# 1400-1a.net
KiCad netlist of a schematic drawn in EAGLE
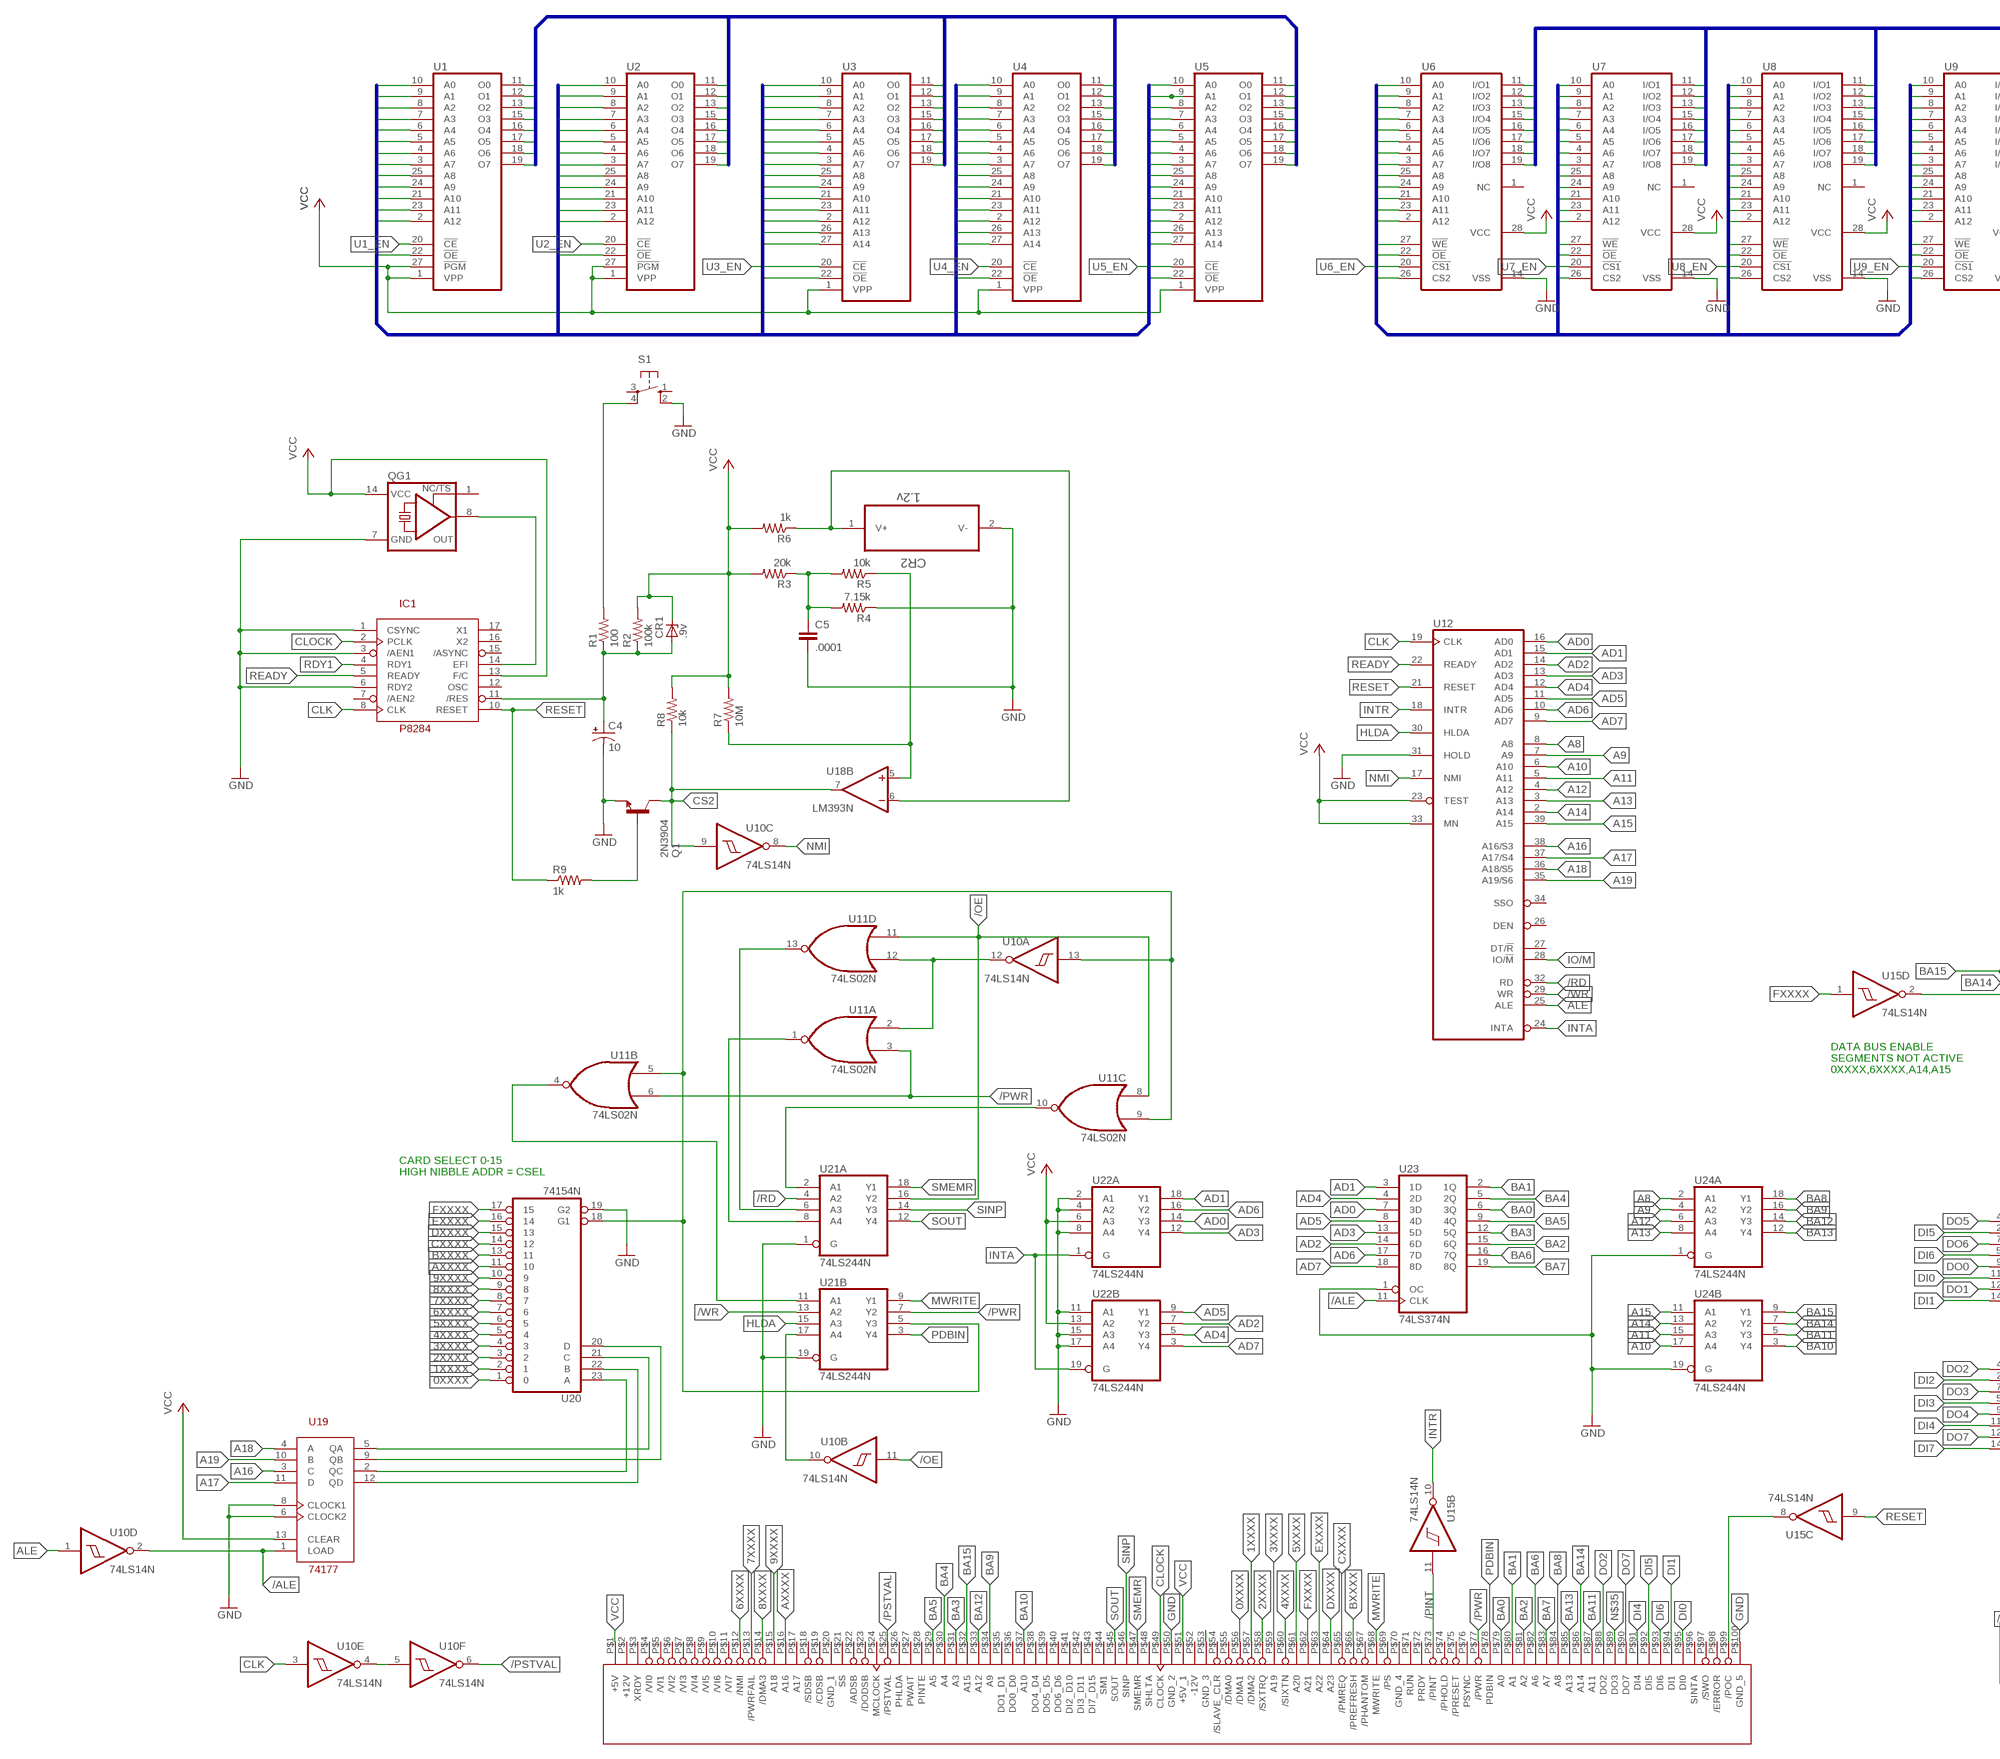
[diagram p0: schematic, sheet 1, part 1 of 2]
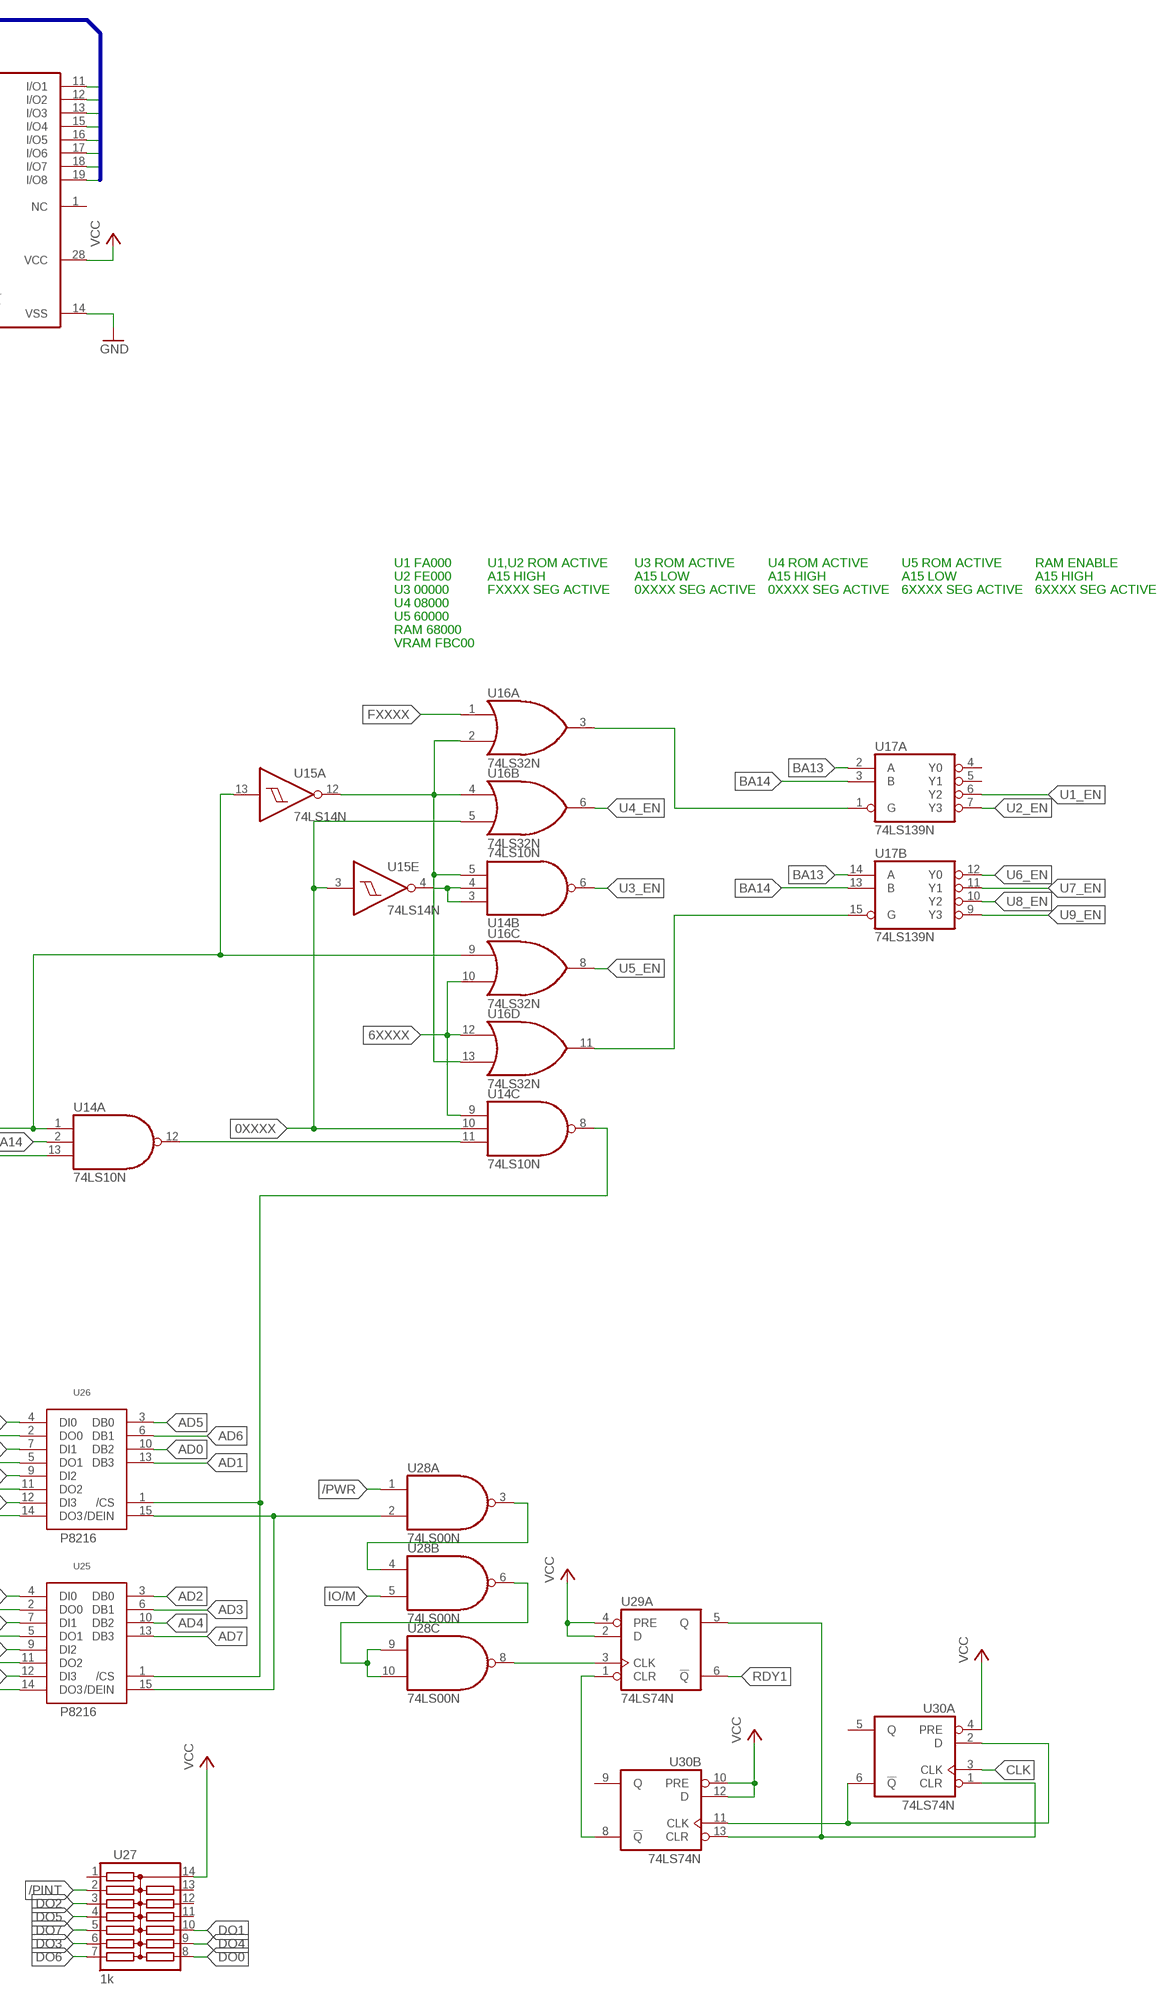
[diagram p1: schematic, sheet 1, part 2 of 2]

(export (version "E")
  (design (tool "Eeschema 10.0.6"))
  (components
    (comp (ref "C4")
      (value "10")
      (footprint "eagle-import:E5-6")
      (libsource (lib "eagle-import") (part "CPOL-USE5-6"))
    )
    (comp (ref "C5")
      (value ".0001")
      (footprint "eagle-import:C050-030X075")
      (libsource (lib "eagle-import") (part "C-EU050-030X075"))
    )
    (comp (ref "CR1")
      (value ".9v")
      (footprint "eagle-import:DO35Z10")
      (libsource (lib "eagle-import") (part "ZTK"))
    )
    (comp (ref "CR2")
      (value "1.2v")
      (footprint "eagle-import:TO127P557X381-2P")
      (fields (field (name "MPN") "AD589TH"))
      (libsource (lib "eagle-import") (part "AD589TH"))
    )
    (comp (ref "IC1")
      (value "P8284")
      (footprint "eagle-import:DIL18")
      (libsource (lib "eagle-import") (part "P8284"))
    )
    (comp (ref "Q1")
      (value "2N3904")
      (footprint "eagle-import:TO92")
      (libsource (lib "eagle-import") (part "2N3904"))
    )
    (comp (ref "QG1")
      (value "XO-14")
      (footprint "eagle-import:DIL14S")
      (libsource (lib "eagle-import") (part "XO-14"))
    )
    (comp (ref "R1")
      (value "100")
      (footprint "eagle-import:0207_12")
      (libsource (lib "eagle-import") (part "R-US_0207/12"))
    )
    (comp (ref "R2")
      (value "100k")
      (footprint "eagle-import:0207_12")
      (libsource (lib "eagle-import") (part "R-US_0207/12"))
    )
    (comp (ref "R3")
      (value "20k")
      (footprint "eagle-import:0207_12")
      (libsource (lib "eagle-import") (part "R-US_0207/12"))
    )
    (comp (ref "R4")
      (value "7.15k")
      (footprint "eagle-import:0207_12")
      (libsource (lib "eagle-import") (part "R-US_0207/12"))
    )
    (comp (ref "R5")
      (value "10k")
      (footprint "eagle-import:0207_12")
      (libsource (lib "eagle-import") (part "R-US_0207/12"))
    )
    (comp (ref "R6")
      (value "1k")
      (footprint "eagle-import:0207_12")
      (libsource (lib "eagle-import") (part "R-US_0207/12"))
    )
    (comp (ref "R7")
      (value "10M")
      (footprint "eagle-import:0207_12")
      (libsource (lib "eagle-import") (part "R-US_0207/12"))
    )
    (comp (ref "R8")
      (value "10k")
      (footprint "eagle-import:0207_12")
      (libsource (lib "eagle-import") (part "R-US_0207/12"))
    )
    (comp (ref "R9")
      (value "1k")
      (footprint "eagle-import:0207_12")
      (libsource (lib "eagle-import") (part "R-US_0207/12"))
    )
    (comp (ref "S1")
      (value "10-XX")
      (footprint "eagle-import:B3F-10XX")
      (fields (field (name "MPN") "B3F-1000"))
      (libsource (lib "eagle-import") (part "10-XX"))
    )
    (comp (ref "U$1")
      (value "S100_MALE")
      (footprint "eagle-import:S100_MALE")
      (libsource (lib "eagle-import") (part "S100_MALE"))
    )
    (comp (ref "U1")
      (value "2764")
      (footprint "eagle-import:DIL28")
      (libsource (lib "eagle-import") (part "2764"))
    )
    (comp (ref "U2")
      (value "2764")
      (footprint "eagle-import:DIL28")
      (libsource (lib "eagle-import") (part "2764"))
    )
    (comp (ref "U3")
      (value "27256")
      (footprint "eagle-import:DIL28")
      (libsource (lib "eagle-import") (part "27256"))
    )
    (comp (ref "U4")
      (value "27256")
      (footprint "eagle-import:DIL28")
      (libsource (lib "eagle-import") (part "27256"))
    )
    (comp (ref "U5")
      (value "27256")
      (footprint "eagle-import:DIL28")
      (libsource (lib "eagle-import") (part "27256"))
    )
    (comp (ref "U6")
      (value "6264A")
      (footprint "eagle-import:DIL28-6")
      (libsource (lib "eagle-import") (part "6264A"))
    )
    (comp (ref "U7")
      (value "6264A")
      (footprint "eagle-import:DIL28-6")
      (libsource (lib "eagle-import") (part "6264A"))
    )
    (comp (ref "U8")
      (value "6264A")
      (footprint "eagle-import:DIL28-6")
      (libsource (lib "eagle-import") (part "6264A"))
    )
    (comp (ref "U9")
      (value "6264A")
      (footprint "eagle-import:DIL28-6")
      (libsource (lib "eagle-import") (part "6264A"))
    )
    (comp (ref "U10")
      (value "74LS14N")
      (footprint "eagle-import:DIL14")
      (libsource (lib "eagle-import") (part "7414NLS"))
    )
    (comp (ref "U11")
      (value "74LS02N")
      (footprint "eagle-import:DIL14")
      (libsource (lib "eagle-import") (part "7402NLS"))
    )
    (comp (ref "U12")
      (value "8088MIN")
      (footprint "eagle-import:DIL40")
      (libsource (lib "eagle-import") (part "8088MIN"))
    )
    (comp (ref "U14")
      (value "74LS10N")
      (footprint "eagle-import:DIL14")
      (libsource (lib "eagle-import") (part "7410NLS"))
    )
    (comp (ref "U15")
      (value "74LS14N")
      (footprint "eagle-import:DIL14")
      (libsource (lib "eagle-import") (part "7414NLS"))
    )
    (comp (ref "U16")
      (value "74LS32N")
      (footprint "eagle-import:DIL14")
      (libsource (lib "eagle-import") (part "7432NLS"))
    )
    (comp (ref "U17")
      (value "74LS139N")
      (footprint "eagle-import:DIL16")
      (libsource (lib "eagle-import") (part "74139NLS"))
    )
    (comp (ref "U18")
      (value "LM393N")
      (footprint "eagle-import:DIL08")
      (libsource (lib "eagle-import") (part "LM393N"))
    )
    (comp (ref "U19")
      (value "74177")
      (footprint "eagle-import:DIL14")
      (libsource (lib "eagle-import") (part "74177"))
    )
    (comp (ref "U20")
      (value "74154N")
      (footprint "eagle-import:DIL24-6")
      (libsource (lib "eagle-import") (part "74154N"))
    )
    (comp (ref "U21")
      (value "74LS244N")
      (footprint "eagle-import:DIL20")
      (libsource (lib "eagle-import") (part "74244NLS"))
    )
    (comp (ref "U22")
      (value "74LS244N")
      (footprint "eagle-import:DIL20")
      (libsource (lib "eagle-import") (part "74244NLS"))
    )
    (comp (ref "U23")
      (value "74LS374N")
      (footprint "eagle-import:DIL20")
      (libsource (lib "eagle-import") (part "74374NLS"))
    )
    (comp (ref "U24")
      (value "74LS244N")
      (footprint "eagle-import:DIL20")
      (libsource (lib "eagle-import") (part "74244NLS"))
    )
    (comp (ref "U25")
      (value "P8216")
      (footprint "eagle-import:DIL16")
      (libsource (lib "eagle-import") (part "P8216"))
    )
    (comp (ref "U26")
      (value "P8216")
      (footprint "eagle-import:DIL16")
      (libsource (lib "eagle-import") (part "P8216"))
    )
    (comp (ref "U27")
      (value "1k")
      (footprint "eagle-import:DIL14")
      (libsource (lib "eagle-import") (part "13R"))
    )
    (comp (ref "U28")
      (value "74LS00N")
      (footprint "eagle-import:DIL14")
      (libsource (lib "eagle-import") (part "7400NLS"))
    )
    (comp (ref "U29")
      (value "74LS74N")
      (footprint "eagle-import:DIL14")
      (libsource (lib "eagle-import") (part "7474NLS"))
    )
    (comp (ref "U30")
      (value "74LS74N")
      (footprint "eagle-import:DIL14")
      (libsource (lib "eagle-import") (part "7474NLS"))
    )
  )
  (nets
    (net (code "1") (name "/+12V") (class "Default")
      (node (ref "U$1") (pin "P$2") (pinfunction "+12V_P$2") (pintype "power_in"))
    )
    (net (code "2") (name "/-12V") (class "Default")
      (node (ref "U$1") (pin "P$52") (pinfunction "-12V_P$52") (pintype "power_in"))
    )
    (net (code "3") (name "/D0") (class "Default")
      (node (ref "U6") (pin "11") (pinfunction "I/O1_11") (pintype "bidirectional"))
      (node (ref "U7") (pin "11") (pinfunction "I/O1_11") (pintype "bidirectional"))
      (node (ref "U8") (pin "11") (pinfunction "I/O1_11") (pintype "bidirectional"))
      (node (ref "U9") (pin "11") (pinfunction "I/O1_11") (pintype "bidirectional"))
    )
    (net (code "4") (name "/D1") (class "Default")
      (node (ref "U6") (pin "12") (pinfunction "I/O2_12") (pintype "bidirectional"))
      (node (ref "U7") (pin "12") (pinfunction "I/O2_12") (pintype "bidirectional"))
      (node (ref "U8") (pin "12") (pinfunction "I/O2_12") (pintype "bidirectional"))
      (node (ref "U9") (pin "12") (pinfunction "I/O2_12") (pintype "bidirectional"))
    )
    (net (code "5") (name "/D2") (class "Default")
      (node (ref "U6") (pin "13") (pinfunction "I/O3_13") (pintype "bidirectional"))
      (node (ref "U7") (pin "13") (pinfunction "I/O3_13") (pintype "bidirectional"))
      (node (ref "U8") (pin "13") (pinfunction "I/O3_13") (pintype "bidirectional"))
      (node (ref "U9") (pin "13") (pinfunction "I/O3_13") (pintype "bidirectional"))
    )
    (net (code "6") (name "/D3") (class "Default")
      (node (ref "U6") (pin "15") (pinfunction "I/O4_15") (pintype "bidirectional"))
      (node (ref "U7") (pin "15") (pinfunction "I/O4_15") (pintype "bidirectional"))
      (node (ref "U8") (pin "15") (pinfunction "I/O4_15") (pintype "bidirectional"))
      (node (ref "U9") (pin "15") (pinfunction "I/O4_15") (pintype "bidirectional"))
    )
    (net (code "7") (name "/D4") (class "Default")
      (node (ref "U6") (pin "16") (pinfunction "I/O5_16") (pintype "bidirectional"))
      (node (ref "U7") (pin "16") (pinfunction "I/O5_16") (pintype "bidirectional"))
      (node (ref "U8") (pin "16") (pinfunction "I/O5_16") (pintype "bidirectional"))
      (node (ref "U9") (pin "16") (pinfunction "I/O5_16") (pintype "bidirectional"))
    )
    (net (code "8") (name "/D5") (class "Default")
      (node (ref "U6") (pin "17") (pinfunction "I/O6_17") (pintype "bidirectional"))
      (node (ref "U7") (pin "17") (pinfunction "I/O6_17") (pintype "bidirectional"))
      (node (ref "U8") (pin "17") (pinfunction "I/O6_17") (pintype "bidirectional"))
      (node (ref "U9") (pin "17") (pinfunction "I/O6_17") (pintype "bidirectional"))
    )
    (net (code "9") (name "/D6") (class "Default")
      (node (ref "U6") (pin "18") (pinfunction "I/O7_18") (pintype "bidirectional"))
      (node (ref "U7") (pin "18") (pinfunction "I/O7_18") (pintype "bidirectional"))
      (node (ref "U8") (pin "18") (pinfunction "I/O7_18") (pintype "bidirectional"))
      (node (ref "U9") (pin "18") (pinfunction "I/O7_18") (pintype "bidirectional"))
    )
    (net (code "10") (name "/D7") (class "Default")
      (node (ref "U6") (pin "19") (pinfunction "I/O8_19") (pintype "bidirectional"))
      (node (ref "U7") (pin "19") (pinfunction "I/O8_19") (pintype "bidirectional"))
      (node (ref "U8") (pin "19") (pinfunction "I/O8_19") (pintype "bidirectional"))
      (node (ref "U9") (pin "19") (pinfunction "I/O8_19") (pintype "bidirectional"))
    )
    (net (code "11") (name "/GND_1") (class "Default")
      (node (ref "U$1") (pin "P$20") (pinfunction "GND_1_P$20") (pintype "power_in"))
    )
    (net (code "12") (name "/GND_4") (class "Default")
      (node (ref "U$1") (pin "P$70") (pinfunction "GND_4_P$70") (pintype "power_in"))
    )
    (net (code "13") (name "0XXXX") (class "Default")
      (node (ref "U$1") (pin "P$56") (pinfunction "/DMA1_P$56") (pintype "bidirectional"))
      (node (ref "U14") (pin "10") (pinfunction "I1_10") (pintype "input"))
      (node (ref "U15") (pin "3") (pinfunction "I_3") (pintype "input"))
      (node (ref "U16") (pin "5") (pinfunction "I1_5") (pintype "input"))
      (node (ref "U20") (pin "1") (pinfunction "0_1") (pintype "output"))
    )
    (net (code "14") (name "1XXXX") (class "Default")
      (node (ref "U$1") (pin "P$57") (pinfunction "/DMA2_P$57") (pintype "bidirectional"))
      (node (ref "U20") (pin "2") (pinfunction "1_2") (pintype "output"))
    )
    (net (code "15") (name "2XXXX") (class "Default")
      (node (ref "U$1") (pin "P$58") (pinfunction "/SXTRQ_P$58") (pintype "bidirectional"))
      (node (ref "U20") (pin "3") (pinfunction "2_3") (pintype "output"))
    )
    (net (code "16") (name "3XXXX") (class "Default")
      (node (ref "U$1") (pin "P$59") (pinfunction "A19_P$59") (pintype "bidirectional"))
      (node (ref "U20") (pin "4") (pinfunction "3_4") (pintype "output"))
    )
    (net (code "17") (name "4XXXX") (class "Default")
      (node (ref "U$1") (pin "P$60") (pinfunction "/SIXTN_P$60") (pintype "bidirectional"))
      (node (ref "U20") (pin "5") (pinfunction "4_5") (pintype "output"))
    )
    (net (code "18") (name "5XXXX") (class "Default")
      (node (ref "U$1") (pin "P$61") (pinfunction "A20_P$61") (pintype "bidirectional"))
      (node (ref "U20") (pin "6") (pinfunction "5_6") (pintype "output"))
    )
    (net (code "19") (name "6XXXX") (class "Default")
      (node (ref "U$1") (pin "P$12") (pinfunction "/NMI_P$12") (pintype "bidirectional"))
      (node (ref "U14") (pin "9") (pinfunction "I0_9") (pintype "input"))
      (node (ref "U16") (pin "10") (pinfunction "I1_10") (pintype "input"))
      (node (ref "U16") (pin "12") (pinfunction "I0_12") (pintype "input"))
      (node (ref "U20") (pin "7") (pinfunction "6_7") (pintype "output"))
    )
    (net (code "20") (name "7XXXX") (class "Default")
      (node (ref "U$1") (pin "P$13") (pinfunction "/PWRFAIL_P$13") (pintype "bidirectional"))
      (node (ref "U20") (pin "8") (pinfunction "7_8") (pintype "output"))
    )
    (net (code "21") (name "8XXXX") (class "Default")
      (node (ref "U$1") (pin "P$14") (pinfunction "/DMA3_P$14") (pintype "bidirectional"))
      (node (ref "U20") (pin "9") (pinfunction "8_9") (pintype "output"))
    )
    (net (code "22") (name "9XXXX") (class "Default")
      (node (ref "U$1") (pin "P$15") (pinfunction "A18_P$15") (pintype "bidirectional"))
      (node (ref "U20") (pin "10") (pinfunction "9_10") (pintype "output"))
    )
    (net (code "23") (name "A8") (class "Default")
      (node (ref "U12") (pin "8") (pinfunction "A8_8") (pintype "bidirectional"))
      (node (ref "U24") (pin "2") (pinfunction "A1_2") (pintype "input"))
    )
    (net (code "24") (name "A9") (class "Default")
      (node (ref "U12") (pin "7") (pinfunction "A9_7") (pintype "bidirectional"))
      (node (ref "U24") (pin "4") (pinfunction "A2_4") (pintype "input"))
    )
    (net (code "25") (name "A10") (class "Default")
      (node (ref "U12") (pin "6") (pinfunction "A10_6") (pintype "bidirectional"))
      (node (ref "U24") (pin "17") (pinfunction "A4_17") (pintype "input"))
    )
    (net (code "26") (name "A11") (class "Default")
      (node (ref "U12") (pin "5") (pinfunction "A11_5") (pintype "bidirectional"))
      (node (ref "U24") (pin "15") (pinfunction "A3_15") (pintype "input"))
    )
    (net (code "27") (name "A12") (class "Default")
      (node (ref "U12") (pin "4") (pinfunction "A12_4") (pintype "bidirectional"))
      (node (ref "U24") (pin "6") (pinfunction "A3_6") (pintype "input"))
    )
    (net (code "28") (name "A13") (class "Default")
      (node (ref "U12") (pin "3") (pinfunction "A13_3") (pintype "bidirectional"))
      (node (ref "U24") (pin "8") (pinfunction "A4_8") (pintype "input"))
    )
    (net (code "29") (name "A14") (class "Default")
      (node (ref "U12") (pin "2") (pinfunction "A14_2") (pintype "bidirectional"))
      (node (ref "U24") (pin "13") (pinfunction "A2_13") (pintype "input"))
    )
    (net (code "30") (name "A15") (class "Default")
      (node (ref "U12") (pin "39") (pinfunction "A15_39") (pintype "bidirectional"))
      (node (ref "U24") (pin "11") (pinfunction "A1_11") (pintype "input"))
    )
    (net (code "31") (name "A16") (class "Default")
      (node (ref "U12") (pin "38") (pinfunction "A16/S3_38") (pintype "output"))
      (node (ref "U19") (pin "3") (pinfunction "C_3") (pintype "bidirectional"))
    )
    (net (code "32") (name "A17") (class "Default")
      (node (ref "U12") (pin "37") (pinfunction "A17/S4_37") (pintype "output"))
      (node (ref "U19") (pin "11") (pinfunction "D_11") (pintype "bidirectional"))
    )
    (net (code "33") (name "A18") (class "Default")
      (node (ref "U12") (pin "36") (pinfunction "A18/S5_36") (pintype "output"))
      (node (ref "U19") (pin "4") (pinfunction "A_4") (pintype "bidirectional"))
    )
    (net (code "34") (name "A19") (class "Default")
      (node (ref "U12") (pin "35") (pinfunction "A19/S6_35") (pintype "output"))
      (node (ref "U19") (pin "10") (pinfunction "B_10") (pintype "bidirectional"))
    )
    (net (code "35") (name "AD0") (class "Default")
      (node (ref "U1") (pin "11") (pinfunction "O0_11") (pintype "tri_state"))
      (node (ref "U12") (pin "16") (pinfunction "AD0_16") (pintype "bidirectional"))
      (node (ref "U2") (pin "11") (pinfunction "O0_11") (pintype "tri_state"))
      (node (ref "U22") (pin "14") (pinfunction "Y3_14") (pintype "tri_state"))
      (node (ref "U23") (pin "7") (pinfunction "3D_7") (pintype "input"))
      (node (ref "U26") (pin "10") (pinfunction "DB2_10") (pintype "bidirectional"))
      (node (ref "U3") (pin "11") (pinfunction "O0_11") (pintype "tri_state"))
      (node (ref "U4") (pin "11") (pinfunction "O0_11") (pintype "tri_state"))
      (node (ref "U5") (pin "11") (pinfunction "O0_11") (pintype "tri_state"))
    )
    (net (code "36") (name "AD1") (class "Default")
      (node (ref "U1") (pin "12") (pinfunction "O1_12") (pintype "tri_state"))
      (node (ref "U12") (pin "15") (pinfunction "AD1_15") (pintype "bidirectional"))
      (node (ref "U2") (pin "12") (pinfunction "O1_12") (pintype "tri_state"))
      (node (ref "U22") (pin "18") (pinfunction "Y1_18") (pintype "tri_state"))
      (node (ref "U23") (pin "3") (pinfunction "1D_3") (pintype "input"))
      (node (ref "U26") (pin "13") (pinfunction "DB3_13") (pintype "bidirectional"))
      (node (ref "U3") (pin "12") (pinfunction "O1_12") (pintype "tri_state"))
      (node (ref "U4") (pin "12") (pinfunction "O1_12") (pintype "tri_state"))
      (node (ref "U5") (pin "12") (pinfunction "O1_12") (pintype "tri_state"))
    )
    (net (code "37") (name "AD2") (class "Default")
      (node (ref "U1") (pin "13") (pinfunction "O2_13") (pintype "tri_state"))
      (node (ref "U12") (pin "14") (pinfunction "AD2_14") (pintype "bidirectional"))
      (node (ref "U2") (pin "13") (pinfunction "O2_13") (pintype "tri_state"))
      (node (ref "U22") (pin "7") (pinfunction "Y2_7") (pintype "tri_state"))
      (node (ref "U23") (pin "14") (pinfunction "6D_14") (pintype "input"))
      (node (ref "U25") (pin "3") (pinfunction "DB0_3") (pintype "bidirectional"))
      (node (ref "U3") (pin "13") (pinfunction "O2_13") (pintype "tri_state"))
      (node (ref "U4") (pin "13") (pinfunction "O2_13") (pintype "tri_state"))
      (node (ref "U5") (pin "13") (pinfunction "O2_13") (pintype "tri_state"))
    )
    (net (code "38") (name "AD3") (class "Default")
      (node (ref "U1") (pin "15") (pinfunction "O3_15") (pintype "tri_state"))
      (node (ref "U12") (pin "13") (pinfunction "AD3_13") (pintype "bidirectional"))
      (node (ref "U2") (pin "15") (pinfunction "O3_15") (pintype "tri_state"))
      (node (ref "U22") (pin "12") (pinfunction "Y4_12") (pintype "tri_state"))
      (node (ref "U23") (pin "13") (pinfunction "5D_13") (pintype "input"))
      (node (ref "U25") (pin "6") (pinfunction "DB1_6") (pintype "bidirectional"))
      (node (ref "U3") (pin "15") (pinfunction "O3_15") (pintype "tri_state"))
      (node (ref "U4") (pin "15") (pinfunction "O3_15") (pintype "tri_state"))
      (node (ref "U5") (pin "15") (pinfunction "O3_15") (pintype "tri_state"))
    )
    (net (code "39") (name "AD4") (class "Default")
      (node (ref "U1") (pin "16") (pinfunction "O4_16") (pintype "tri_state"))
      (node (ref "U12") (pin "12") (pinfunction "AD4_12") (pintype "bidirectional"))
      (node (ref "U2") (pin "16") (pinfunction "O4_16") (pintype "tri_state"))
      (node (ref "U22") (pin "5") (pinfunction "Y3_5") (pintype "tri_state"))
      (node (ref "U23") (pin "4") (pinfunction "2D_4") (pintype "input"))
      (node (ref "U25") (pin "10") (pinfunction "DB2_10") (pintype "bidirectional"))
      (node (ref "U3") (pin "16") (pinfunction "O4_16") (pintype "tri_state"))
      (node (ref "U4") (pin "16") (pinfunction "O4_16") (pintype "tri_state"))
      (node (ref "U5") (pin "16") (pinfunction "O4_16") (pintype "tri_state"))
    )
    (net (code "40") (name "AD5") (class "Default")
      (node (ref "U1") (pin "17") (pinfunction "O5_17") (pintype "tri_state"))
      (node (ref "U12") (pin "11") (pinfunction "AD5_11") (pintype "bidirectional"))
      (node (ref "U2") (pin "17") (pinfunction "O5_17") (pintype "tri_state"))
      (node (ref "U22") (pin "9") (pinfunction "Y1_9") (pintype "tri_state"))
      (node (ref "U23") (pin "8") (pinfunction "4D_8") (pintype "input"))
      (node (ref "U26") (pin "3") (pinfunction "DB0_3") (pintype "bidirectional"))
      (node (ref "U3") (pin "17") (pinfunction "O5_17") (pintype "tri_state"))
      (node (ref "U4") (pin "17") (pinfunction "O5_17") (pintype "tri_state"))
      (node (ref "U5") (pin "17") (pinfunction "O5_17") (pintype "tri_state"))
    )
    (net (code "41") (name "AD6") (class "Default")
      (node (ref "U1") (pin "18") (pinfunction "O6_18") (pintype "tri_state"))
      (node (ref "U12") (pin "10") (pinfunction "AD6_10") (pintype "bidirectional"))
      (node (ref "U2") (pin "18") (pinfunction "O6_18") (pintype "tri_state"))
      (node (ref "U22") (pin "16") (pinfunction "Y2_16") (pintype "tri_state"))
      (node (ref "U23") (pin "17") (pinfunction "7D_17") (pintype "input"))
      (node (ref "U26") (pin "6") (pinfunction "DB1_6") (pintype "bidirectional"))
      (node (ref "U3") (pin "18") (pinfunction "O6_18") (pintype "tri_state"))
      (node (ref "U4") (pin "18") (pinfunction "O6_18") (pintype "tri_state"))
      (node (ref "U5") (pin "18") (pinfunction "O6_18") (pintype "tri_state"))
    )
    (net (code "42") (name "AD7") (class "Default")
      (node (ref "U1") (pin "19") (pinfunction "O7_19") (pintype "tri_state"))
      (node (ref "U12") (pin "9") (pinfunction "AD7_9") (pintype "bidirectional"))
      (node (ref "U2") (pin "19") (pinfunction "O7_19") (pintype "tri_state"))
      (node (ref "U22") (pin "3") (pinfunction "Y4_3") (pintype "tri_state"))
      (node (ref "U23") (pin "18") (pinfunction "8D_18") (pintype "input"))
      (node (ref "U25") (pin "13") (pinfunction "DB3_13") (pintype "bidirectional"))
      (node (ref "U3") (pin "19") (pinfunction "O7_19") (pintype "tri_state"))
      (node (ref "U4") (pin "19") (pinfunction "O7_19") (pintype "tri_state"))
      (node (ref "U5") (pin "19") (pinfunction "O7_19") (pintype "tri_state"))
    )
    (net (code "43") (name "ALE") (class "Default")
      (node (ref "U10") (pin "1") (pinfunction "I_1") (pintype "input"))
      (node (ref "U12") (pin "25") (pinfunction "ALE_25") (pintype "output"))
    )
    (net (code "44") (name "AXXXX") (class "Default")
      (node (ref "U$1") (pin "P$16") (pinfunction "A16_P$16") (pintype "bidirectional"))
      (node (ref "U20") (pin "11") (pinfunction "10_11") (pintype "output"))
    )
    (net (code "45") (name "BA0") (class "Default")
      (node (ref "U$1") (pin "P$79") (pinfunction "A0_P$79") (pintype "bidirectional"))
      (node (ref "U1") (pin "10") (pinfunction "A0_10") (pintype "input"))
      (node (ref "U2") (pin "10") (pinfunction "A0_10") (pintype "input"))
      (node (ref "U23") (pin "6") (pinfunction "3Q_6") (pintype "tri_state"))
      (node (ref "U3") (pin "10") (pinfunction "A0_10") (pintype "input"))
      (node (ref "U4") (pin "10") (pinfunction "A0_10") (pintype "input"))
      (node (ref "U5") (pin "10") (pinfunction "A0_10") (pintype "input"))
      (node (ref "U6") (pin "10") (pinfunction "A0_10") (pintype "input"))
      (node (ref "U7") (pin "10") (pinfunction "A0_10") (pintype "input"))
      (node (ref "U8") (pin "10") (pinfunction "A0_10") (pintype "input"))
      (node (ref "U9") (pin "10") (pinfunction "A0_10") (pintype "input"))
    )
    (net (code "46") (name "BA1") (class "Default")
      (node (ref "U$1") (pin "P$80") (pinfunction "A1_P$80") (pintype "bidirectional"))
      (node (ref "U1") (pin "9") (pinfunction "A1_9") (pintype "input"))
      (node (ref "U2") (pin "9") (pinfunction "A1_9") (pintype "input"))
      (node (ref "U23") (pin "2") (pinfunction "1Q_2") (pintype "tri_state"))
      (node (ref "U3") (pin "7") (pinfunction "A3_7") (pintype "input"))
      (node (ref "U3") (pin "9") (pinfunction "A1_9") (pintype "input"))
      (node (ref "U4") (pin "9") (pinfunction "A1_9") (pintype "input"))
      (node (ref "U5") (pin "9") (pinfunction "A1_9") (pintype "input"))
      (node (ref "U6") (pin "9") (pinfunction "A1_9") (pintype "input"))
      (node (ref "U7") (pin "9") (pinfunction "A1_9") (pintype "input"))
      (node (ref "U8") (pin "9") (pinfunction "A1_9") (pintype "input"))
      (node (ref "U9") (pin "9") (pinfunction "A1_9") (pintype "input"))
    )
    (net (code "47") (name "BA2") (class "Default")
      (node (ref "U$1") (pin "P$81") (pinfunction "A2_P$81") (pintype "bidirectional"))
      (node (ref "U1") (pin "8") (pinfunction "A2_8") (pintype "input"))
      (node (ref "U2") (pin "8") (pinfunction "A2_8") (pintype "input"))
      (node (ref "U23") (pin "15") (pinfunction "6Q_15") (pintype "tri_state"))
      (node (ref "U3") (pin "8") (pinfunction "A2_8") (pintype "input"))
      (node (ref "U4") (pin "8") (pinfunction "A2_8") (pintype "input"))
      (node (ref "U5") (pin "8") (pinfunction "A2_8") (pintype "input"))
      (node (ref "U6") (pin "8") (pinfunction "A2_8") (pintype "input"))
      (node (ref "U7") (pin "8") (pinfunction "A2_8") (pintype "input"))
      (node (ref "U8") (pin "8") (pinfunction "A2_8") (pintype "input"))
      (node (ref "U9") (pin "8") (pinfunction "A2_8") (pintype "input"))
    )
    (net (code "48") (name "BA3") (class "Default")
      (node (ref "U$1") (pin "P$31") (pinfunction "A3_P$31") (pintype "bidirectional"))
      (node (ref "U1") (pin "7") (pinfunction "A3_7") (pintype "input"))
      (node (ref "U2") (pin "7") (pinfunction "A3_7") (pintype "input"))
      (node (ref "U23") (pin "12") (pinfunction "5Q_12") (pintype "tri_state"))
      (node (ref "U4") (pin "7") (pinfunction "A3_7") (pintype "input"))
      (node (ref "U5") (pin "7") (pinfunction "A3_7") (pintype "input"))
      (node (ref "U6") (pin "7") (pinfunction "A3_7") (pintype "input"))
      (node (ref "U7") (pin "7") (pinfunction "A3_7") (pintype "input"))
      (node (ref "U8") (pin "7") (pinfunction "A3_7") (pintype "input"))
      (node (ref "U9") (pin "7") (pinfunction "A3_7") (pintype "input"))
    )
    (net (code "49") (name "BA4") (class "Default")
      (node (ref "U$1") (pin "P$30") (pinfunction "A4_P$30") (pintype "bidirectional"))
      (node (ref "U1") (pin "6") (pinfunction "A4_6") (pintype "input"))
      (node (ref "U2") (pin "6") (pinfunction "A4_6") (pintype "input"))
      (node (ref "U23") (pin "5") (pinfunction "2Q_5") (pintype "tri_state"))
      (node (ref "U3") (pin "6") (pinfunction "A4_6") (pintype "input"))
      (node (ref "U4") (pin "6") (pinfunction "A4_6") (pintype "input"))
      (node (ref "U5") (pin "6") (pinfunction "A4_6") (pintype "input"))
      (node (ref "U6") (pin "6") (pinfunction "A4_6") (pintype "input"))
      (node (ref "U7") (pin "6") (pinfunction "A4_6") (pintype "input"))
      (node (ref "U8") (pin "6") (pinfunction "A4_6") (pintype "input"))
      (node (ref "U9") (pin "6") (pinfunction "A4_6") (pintype "input"))
    )
    (net (code "50") (name "BA5") (class "Default")
      (node (ref "U$1") (pin "P$29") (pinfunction "A5_P$29") (pintype "bidirectional"))
      (node (ref "U1") (pin "5") (pinfunction "A5_5") (pintype "input"))
      (node (ref "U2") (pin "5") (pinfunction "A5_5") (pintype "input"))
      (node (ref "U23") (pin "9") (pinfunction "4Q_9") (pintype "tri_state"))
      (node (ref "U3") (pin "5") (pinfunction "A5_5") (pintype "input"))
      (node (ref "U4") (pin "5") (pinfunction "A5_5") (pintype "input"))
      (node (ref "U5") (pin "5") (pinfunction "A5_5") (pintype "input"))
      (node (ref "U6") (pin "5") (pinfunction "A5_5") (pintype "input"))
      (node (ref "U7") (pin "5") (pinfunction "A5_5") (pintype "input"))
      (node (ref "U8") (pin "5") (pinfunction "A5_5") (pintype "input"))
      (node (ref "U9") (pin "5") (pinfunction "A5_5") (pintype "input"))
    )
    (net (code "51") (name "BA6") (class "Default")
      (node (ref "U$1") (pin "P$82") (pinfunction "A6_P$82") (pintype "bidirectional"))
      (node (ref "U1") (pin "4") (pinfunction "A6_4") (pintype "input"))
      (node (ref "U2") (pin "4") (pinfunction "A6_4") (pintype "input"))
      (node (ref "U23") (pin "16") (pinfunction "7Q_16") (pintype "tri_state"))
      (node (ref "U3") (pin "4") (pinfunction "A6_4") (pintype "input"))
      (node (ref "U4") (pin "4") (pinfunction "A6_4") (pintype "input"))
      (node (ref "U5") (pin "4") (pinfunction "A6_4") (pintype "input"))
      (node (ref "U6") (pin "4") (pinfunction "A6_4") (pintype "input"))
      (node (ref "U7") (pin "4") (pinfunction "A6_4") (pintype "input"))
      (node (ref "U8") (pin "4") (pinfunction "A6_4") (pintype "input"))
      (node (ref "U9") (pin "4") (pinfunction "A6_4") (pintype "input"))
    )
    (net (code "52") (name "BA7") (class "Default")
      (node (ref "U$1") (pin "P$83") (pinfunction "A7_P$83") (pintype "bidirectional"))
      (node (ref "U1") (pin "3") (pinfunction "A7_3") (pintype "input"))
      (node (ref "U2") (pin "3") (pinfunction "A7_3") (pintype "input"))
      (node (ref "U23") (pin "19") (pinfunction "8Q_19") (pintype "tri_state"))
      (node (ref "U3") (pin "3") (pinfunction "A7_3") (pintype "input"))
      (node (ref "U4") (pin "3") (pinfunction "A7_3") (pintype "input"))
      (node (ref "U5") (pin "3") (pinfunction "A7_3") (pintype "input"))
      (node (ref "U6") (pin "3") (pinfunction "A7_3") (pintype "input"))
      (node (ref "U7") (pin "3") (pinfunction "A7_3") (pintype "input"))
      (node (ref "U8") (pin "3") (pinfunction "A7_3") (pintype "input"))
      (node (ref "U9") (pin "3") (pinfunction "A7_3") (pintype "input"))
    )
    (net (code "53") (name "BA8") (class "Default")
      (node (ref "U$1") (pin "P$84") (pinfunction "A8_P$84") (pintype "bidirectional"))
      (node (ref "U1") (pin "25") (pinfunction "A8_25") (pintype "input"))
      (node (ref "U2") (pin "25") (pinfunction "A8_25") (pintype "input"))
      (node (ref "U24") (pin "18") (pinfunction "Y1_18") (pintype "tri_state"))
      (node (ref "U3") (pin "25") (pinfunction "A8_25") (pintype "input"))
      (node (ref "U4") (pin "25") (pinfunction "A8_25") (pintype "input"))
      (node (ref "U5") (pin "25") (pinfunction "A8_25") (pintype "input"))
      (node (ref "U6") (pin "25") (pinfunction "A8_25") (pintype "input"))
      (node (ref "U7") (pin "25") (pinfunction "A8_25") (pintype "input"))
      (node (ref "U8") (pin "25") (pinfunction "A8_25") (pintype "input"))
      (node (ref "U9") (pin "25") (pinfunction "A8_25") (pintype "input"))
    )
    (net (code "54") (name "BA9") (class "Default")
      (node (ref "U$1") (pin "P$34") (pinfunction "A9_P$34") (pintype "bidirectional"))
      (node (ref "U1") (pin "24") (pinfunction "A9_24") (pintype "input"))
      (node (ref "U2") (pin "24") (pinfunction "A9_24") (pintype "input"))
      (node (ref "U24") (pin "16") (pinfunction "Y2_16") (pintype "tri_state"))
      (node (ref "U3") (pin "24") (pinfunction "A9_24") (pintype "input"))
      (node (ref "U4") (pin "24") (pinfunction "A9_24") (pintype "input"))
      (node (ref "U5") (pin "24") (pinfunction "A9_24") (pintype "input"))
      (node (ref "U6") (pin "24") (pinfunction "A9_24") (pintype "input"))
      (node (ref "U7") (pin "24") (pinfunction "A9_24") (pintype "input"))
      (node (ref "U8") (pin "24") (pinfunction "A9_24") (pintype "input"))
      (node (ref "U9") (pin "24") (pinfunction "A9_24") (pintype "input"))
    )
    (net (code "55") (name "BA10") (class "Default")
      (node (ref "U$1") (pin "P$37") (pinfunction "A10_P$37") (pintype "bidirectional"))
      (node (ref "U1") (pin "21") (pinfunction "A10_21") (pintype "input"))
      (node (ref "U2") (pin "21") (pinfunction "A10_21") (pintype "input"))
      (node (ref "U24") (pin "3") (pinfunction "Y4_3") (pintype "tri_state"))
      (node (ref "U3") (pin "21") (pinfunction "A10_21") (pintype "input"))
      (node (ref "U4") (pin "21") (pinfunction "A10_21") (pintype "input"))
      (node (ref "U5") (pin "21") (pinfunction "A10_21") (pintype "input"))
      (node (ref "U6") (pin "21") (pinfunction "A10_21") (pintype "input"))
      (node (ref "U7") (pin "21") (pinfunction "A10_21") (pintype "input"))
      (node (ref "U8") (pin "21") (pinfunction "A10_21") (pintype "input"))
      (node (ref "U9") (pin "21") (pinfunction "A10_21") (pintype "input"))
    )
    (net (code "56") (name "BA11") (class "Default")
      (node (ref "U$1") (pin "P$87") (pinfunction "A11_P$87") (pintype "bidirectional"))
      (node (ref "U1") (pin "23") (pinfunction "A11_23") (pintype "input"))
      (node (ref "U2") (pin "23") (pinfunction "A11_23") (pintype "input"))
      (node (ref "U24") (pin "5") (pinfunction "Y3_5") (pintype "tri_state"))
      (node (ref "U3") (pin "23") (pinfunction "A11_23") (pintype "input"))
      (node (ref "U4") (pin "23") (pinfunction "A11_23") (pintype "input"))
      (node (ref "U5") (pin "23") (pinfunction "A11_23") (pintype "input"))
      (node (ref "U6") (pin "23") (pinfunction "A11_23") (pintype "input"))
      (node (ref "U7") (pin "23") (pinfunction "A11_23") (pintype "input"))
      (node (ref "U8") (pin "23") (pinfunction "A11_23") (pintype "input"))
      (node (ref "U9") (pin "23") (pinfunction "A11_23") (pintype "input"))
    )
    (net (code "57") (name "BA12") (class "Default")
      (node (ref "U$1") (pin "P$33") (pinfunction "A12_P$33") (pintype "bidirectional"))
      (node (ref "U1") (pin "2") (pinfunction "A12_2") (pintype "input"))
      (node (ref "U2") (pin "2") (pinfunction "A12_2") (pintype "input"))
      (node (ref "U24") (pin "14") (pinfunction "Y3_14") (pintype "tri_state"))
      (node (ref "U3") (pin "2") (pinfunction "A12_2") (pintype "input"))
      (node (ref "U4") (pin "2") (pinfunction "A12_2") (pintype "input"))
      (node (ref "U5") (pin "2") (pinfunction "A12_2") (pintype "input"))
      (node (ref "U6") (pin "2") (pinfunction "A12_2") (pintype "input"))
      (node (ref "U7") (pin "2") (pinfunction "A12_2") (pintype "input"))
      (node (ref "U8") (pin "2") (pinfunction "A12_2") (pintype "input"))
      (node (ref "U9") (pin "2") (pinfunction "A12_2") (pintype "input"))
    )
    (net (code "58") (name "BA13") (class "Default")
      (node (ref "U$1") (pin "P$85") (pinfunction "A13_P$85") (pintype "bidirectional"))
      (node (ref "U17") (pin "14") (pinfunction "A_14") (pintype "input"))
      (node (ref "U17") (pin "2") (pinfunction "A_2") (pintype "input"))
      (node (ref "U24") (pin "12") (pinfunction "Y4_12") (pintype "tri_state"))
      (node (ref "U3") (pin "26") (pinfunction "A13_26") (pintype "input"))
      (node (ref "U4") (pin "26") (pinfunction "A13_26") (pintype "input"))
      (node (ref "U5") (pin "26") (pinfunction "A13_26") (pintype "input"))
    )
    (net (code "59") (name "BA14") (class "Default")
      (node (ref "U$1") (pin "P$86") (pinfunction "A14_P$86") (pintype "bidirectional"))
      (node (ref "U14") (pin "2") (pinfunction "I1_2") (pintype "input"))
      (node (ref "U17") (pin "13") (pinfunction "B_13") (pintype "input"))
      (node (ref "U17") (pin "3") (pinfunction "B_3") (pintype "input"))
      (node (ref "U24") (pin "7") (pinfunction "Y2_7") (pintype "tri_state"))
      (node (ref "U3") (pin "27") (pinfunction "A14_27") (pintype "input"))
      (node (ref "U4") (pin "27") (pinfunction "A14_27") (pintype "input"))
      (node (ref "U5") (pin "27") (pinfunction "A14_27") (pintype "input"))
    )
    (net (code "60") (name "BA15") (class "Default")
      (node (ref "U$1") (pin "P$32") (pinfunction "A15_P$32") (pintype "bidirectional"))
      (node (ref "U14") (pin "1") (pinfunction "I0_1") (pintype "input"))
      (node (ref "U15") (pin "13") (pinfunction "I_13") (pintype "input"))
      (node (ref "U16") (pin "9") (pinfunction "I0_9") (pintype "input"))
      (node (ref "U24") (pin "9") (pinfunction "Y1_9") (pintype "tri_state"))
    )
    (net (code "61") (name "BXXXX") (class "Default")
      (node (ref "U$1") (pin "P$66") (pinfunction "/PREFRESH_P$66") (pintype "bidirectional"))
      (node (ref "U20") (pin "13") (pinfunction "11_13") (pintype "output"))
    )
    (net (code "62") (name "CLK") (class "Default")
      (node (ref "IC1") (pin "8") (pinfunction "CLK_8") (pintype "bidirectional"))
      (node (ref "U10") (pin "3") (pinfunction "I_3") (pintype "input"))
      (node (ref "U12") (pin "19") (pinfunction "CLK_19") (pintype "input"))
      (node (ref "U30") (pin "3") (pinfunction "CLK_3") (pintype "input"))
    )
    (net (code "63") (name "CLOCK") (class "Default")
      (node (ref "IC1") (pin "2") (pinfunction "PCLK_2") (pintype "bidirectional"))
      (node (ref "U$1") (pin "P$49") (pinfunction "CLOCK_P$49") (pintype "bidirectional"))
    )
    (net (code "64") (name "CS2") (class "Default")
      (node (ref "Q1") (pin "1") (pinfunction "C_1") (pintype "passive"))
      (node (ref "R8") (pin "1") (pinfunction "1_1") (pintype "passive"))
      (node (ref "U10") (pin "9") (pinfunction "I_9") (pintype "input"))
      (node (ref "U18") (pin "7") (pinfunction "OUT_7") (pintype "output"))
      (node (ref "U6") (pin "26") (pinfunction "CS2_26") (pintype "input"))
      (node (ref "U7") (pin "26") (pinfunction "CS2_26") (pintype "input"))
      (node (ref "U8") (pin "26") (pinfunction "CS2_26") (pintype "input"))
      (node (ref "U9") (pin "26") (pinfunction "CS2_26") (pintype "input"))
    )
    (net (code "65") (name "CXXXX") (class "Default")
      (node (ref "U$1") (pin "P$65") (pinfunction "/PMREQ_P$65") (pintype "bidirectional"))
      (node (ref "U20") (pin "14") (pinfunction "12_14") (pintype "output"))
    )
    (net (code "66") (name "DI0") (class "Default")
      (node (ref "U$1") (pin "P$95") (pinfunction "DI0_P$95") (pintype "bidirectional"))
      (node (ref "U26") (pin "11") (pinfunction "DO2_11") (pintype "bidirectional"))
    )
    (net (code "67") (name "DI1") (class "Default")
      (node (ref "U$1") (pin "P$94") (pinfunction "DI1_P$94") (pintype "bidirectional"))
      (node (ref "U26") (pin "14") (pinfunction "DO3_14") (pintype "bidirectional"))
    )
    (net (code "68") (name "DI2") (class "Default")
      (node (ref "U25") (pin "2") (pinfunction "DO0_2") (pintype "bidirectional"))
    )
    (net (code "69") (name "DI3") (class "Default")
      (node (ref "U25") (pin "5") (pinfunction "DO1_5") (pintype "bidirectional"))
    )
    (net (code "70") (name "DI4") (class "Default")
      (node (ref "U$1") (pin "P$91") (pinfunction "DI4_P$91") (pintype "bidirectional"))
      (node (ref "U25") (pin "11") (pinfunction "DO2_11") (pintype "bidirectional"))
    )
    (net (code "71") (name "DI5") (class "Default")
      (node (ref "U$1") (pin "P$92") (pinfunction "DI5_P$92") (pintype "bidirectional"))
      (node (ref "U26") (pin "2") (pinfunction "DO0_2") (pintype "bidirectional"))
    )
    (net (code "72") (name "DI6") (class "Default")
      (node (ref "U$1") (pin "P$93") (pinfunction "DI6_P$93") (pintype "bidirectional"))
      (node (ref "U26") (pin "5") (pinfunction "DO1_5") (pintype "bidirectional"))
    )
    (net (code "73") (name "DI7") (class "Default")
      (node (ref "U25") (pin "14") (pinfunction "DO3_14") (pintype "bidirectional"))
    )
    (net (code "74") (name "DO0") (class "Default")
      (node (ref "U26") (pin "9") (pinfunction "DI2_9") (pintype "bidirectional"))
      (node (ref "U27") (pin "8") (pinfunction "8_8") (pintype "passive"))
    )
    (net (code "75") (name "DO1") (class "Default")
      (node (ref "U26") (pin "12") (pinfunction "DI3_12") (pintype "bidirectional"))
      (node (ref "U27") (pin "10") (pinfunction "10_10") (pintype "passive"))
    )
    (net (code "76") (name "DO2") (class "Default")
      (node (ref "U$1") (pin "P$88") (pinfunction "DO2_P$88") (pintype "bidirectional"))
      (node (ref "U25") (pin "4") (pinfunction "DI0_4") (pintype "bidirectional"))
      (node (ref "U27") (pin "3") (pinfunction "3_3") (pintype "passive"))
    )
    (net (code "77") (name "DO3") (class "Default")
      (node (ref "U25") (pin "7") (pinfunction "DI1_7") (pintype "bidirectional"))
      (node (ref "U27") (pin "6") (pinfunction "6_6") (pintype "passive"))
    )
    (net (code "78") (name "DO4") (class "Default")
      (node (ref "U25") (pin "9") (pinfunction "DI2_9") (pintype "bidirectional"))
      (node (ref "U27") (pin "9") (pinfunction "9_9") (pintype "passive"))
    )
    (net (code "79") (name "DO5") (class "Default")
      (node (ref "U26") (pin "4") (pinfunction "DI0_4") (pintype "bidirectional"))
      (node (ref "U27") (pin "4") (pinfunction "4_4") (pintype "passive"))
    )
    (net (code "80") (name "DO6") (class "Default")
      (node (ref "U26") (pin "7") (pinfunction "DI1_7") (pintype "bidirectional"))
      (node (ref "U27") (pin "7") (pinfunction "7_7") (pintype "passive"))
    )
    (net (code "81") (name "DO7") (class "Default")
      (node (ref "U$1") (pin "P$90") (pinfunction "DO7_P$90") (pintype "bidirectional"))
      (node (ref "U25") (pin "12") (pinfunction "DI3_12") (pintype "bidirectional"))
      (node (ref "U27") (pin "5") (pinfunction "5_5") (pintype "passive"))
    )
    (net (code "82") (name "DXXXX") (class "Default")
      (node (ref "U$1") (pin "P$64") (pinfunction "A23_P$64") (pintype "bidirectional"))
      (node (ref "U20") (pin "15") (pinfunction "13_15") (pintype "output"))
    )
    (net (code "83") (name "EXXXX") (class "Default")
      (node (ref "U$1") (pin "P$63") (pinfunction "A22_P$63") (pintype "bidirectional"))
      (node (ref "U20") (pin "16") (pinfunction "14_16") (pintype "output"))
    )
    (net (code "84") (name "FXXXX") (class "Default")
      (node (ref "U$1") (pin "P$62") (pinfunction "A21_P$62") (pintype "bidirectional"))
      (node (ref "U15") (pin "1") (pinfunction "I_1") (pintype "input"))
      (node (ref "U16") (pin "1") (pinfunction "I0_1") (pintype "input"))
      (node (ref "U20") (pin "17") (pinfunction "15_17") (pintype "output"))
    )
    (net (code "85") (name "GND") (class "Default")
      (node (ref "C4") (pin "-") (pinfunction "-_-") (pintype "passive"))
      (node (ref "C5") (pin "2") (pinfunction "2_2") (pintype "passive"))
      (node (ref "CR2") (pin "2") (pinfunction "V-_2") (pintype "passive"))
      (node (ref "IC1") (pin "1") (pinfunction "CSYNC_1") (pintype "bidirectional"))
      (node (ref "IC1") (pin "3") (pinfunction "/AEN1_3") (pintype "bidirectional"))
      (node (ref "IC1") (pin "6") (pinfunction "RDY2_6") (pintype "bidirectional"))
      (node (ref "Q1") (pin "3") (pinfunction "E_3") (pintype "passive"))
      (node (ref "QG1") (pin "7") (pinfunction "GND_7") (pintype "power_in"))
      (node (ref "R4") (pin "1") (pinfunction "1_1") (pintype "passive"))
      (node (ref "S1") (pin "2") (pinfunction "S1_2") (pintype "passive"))
      (node (ref "U$1") (pin "P$100") (pinfunction "GND_5_P$100") (pintype "power_in"))
      (node (ref "U$1") (pin "P$50") (pinfunction "GND_2_P$50") (pintype "power_in"))
      (node (ref "U12") (pin "31") (pinfunction "HOLD_31") (pintype "input"))
      (node (ref "U19") (pin "6") (pinfunction "CLOCK2_6") (pintype "bidirectional"))
      (node (ref "U19") (pin "8") (pinfunction "CLOCK1_8") (pintype "bidirectional"))
      (node (ref "U20") (pin "19") (pinfunction "G2_19") (pintype "input"))
      (node (ref "U21") (pin "1") (pinfunction "G_1") (pintype "input"))
      (node (ref "U21") (pin "19") (pinfunction "G_19") (pintype "input"))
      (node (ref "U22") (pin "11") (pinfunction "A1_11") (pintype "input"))
      (node (ref "U22") (pin "15") (pinfunction "A3_15") (pintype "input"))
      (node (ref "U22") (pin "17") (pinfunction "A4_17") (pintype "input"))
      (node (ref "U22") (pin "2") (pinfunction "A1_2") (pintype "input"))
      (node (ref "U22") (pin "4") (pinfunction "A2_4") (pintype "input"))
      (node (ref "U22") (pin "8") (pinfunction "A4_8") (pintype "input"))
      (node (ref "U23") (pin "1") (pinfunction "OC_1") (pintype "input"))
      (node (ref "U24") (pin "1") (pinfunction "G_1") (pintype "input"))
      (node (ref "U24") (pin "19") (pinfunction "G_19") (pintype "input"))
      (node (ref "U6") (pin "14") (pinfunction "VSS_14") (pintype "power_in"))
      (node (ref "U7") (pin "14") (pinfunction "VSS_14") (pintype "power_in"))
      (node (ref "U8") (pin "14") (pinfunction "VSS_14") (pintype "power_in"))
      (node (ref "U9") (pin "14") (pinfunction "VSS_14") (pintype "power_in"))
    )
    (net (code "86") (name "HLDA") (class "Default")
      (node (ref "U12") (pin "30") (pinfunction "HLDA_30") (pintype "output"))
      (node (ref "U21") (pin "15") (pinfunction "A3_15") (pintype "input"))
    )
    (net (code "87") (name "INTA") (class "Default")
      (node (ref "U12") (pin "24") (pinfunction "INTA_24") (pintype "output"))
      (node (ref "U22") (pin "1") (pinfunction "G_1") (pintype "input"))
      (node (ref "U22") (pin "19") (pinfunction "G_19") (pintype "input"))
    )
    (net (code "88") (name "INTR") (class "Default")
      (node (ref "U12") (pin "18") (pinfunction "INTR_18") (pintype "input"))
      (node (ref "U15") (pin "10") (pinfunction "O_10") (pintype "output"))
    )
    (net (code "89") (name "IO{slash}M") (class "Default")
      (node (ref "U12") (pin "28") (pinfunction "IO/~{M}_28") (pintype "output"))
      (node (ref "U28") (pin "5") (pinfunction "I1_5") (pintype "input"))
    )
    (net (code "90") (name "MWRITE") (class "Default")
      (node (ref "U$1") (pin "P$68") (pinfunction "MWRITE_P$68") (pintype "bidirectional"))
      (node (ref "U21") (pin "9") (pinfunction "Y1_9") (pintype "tri_state"))
    )
    (net (code "91") (name "N$35") (class "Default")
      (node (ref "U$1") (pin "P$89") (pinfunction "DO3_P$89") (pintype "bidirectional"))
    )
    (net (code "92") (name "NMI") (class "Default")
      (node (ref "U10") (pin "8") (pinfunction "O_8") (pintype "output"))
      (node (ref "U12") (pin "17") (pinfunction "NMI_17") (pintype "input"))
    )
    (net (code "93") (name "Net-(C5-Pad1)") (class "Default")
      (node (ref "C5") (pin "1") (pinfunction "1_1") (pintype "passive"))
      (node (ref "R3") (pin "1") (pinfunction "1_1") (pintype "passive"))
      (node (ref "R4") (pin "2") (pinfunction "2_2") (pintype "passive"))
      (node (ref "R5") (pin "2") (pinfunction "2_2") (pintype "passive"))
    )
    (net (code "94") (name "Net-(CR2-V+)") (class "Default")
      (node (ref "CR2") (pin "1") (pinfunction "V+_1") (pintype "passive"))
      (node (ref "R6") (pin "1") (pinfunction "1_1") (pintype "passive"))
      (node (ref "U18") (pin "6") (pinfunction "-IN_6") (pintype "input"))
    )
    (net (code "95") (name "Net-(IC1A-EFI)") (class "Default")
      (node (ref "IC1") (pin "14") (pinfunction "EFI_14") (pintype "bidirectional"))
      (node (ref "QG1") (pin "8") (pinfunction "OUT_8") (pintype "output"))
    )
    (net (code "96") (name "Net-(IC1A-{slash}RES)") (class "Default")
      (node (ref "C4") (pin "+") (pinfunction "+_+") (pintype "passive"))
      (node (ref "CR1") (pin "A") (pinfunction "A_A") (pintype "passive"))
      (node (ref "IC1") (pin "11") (pinfunction "/RES_11") (pintype "bidirectional"))
      (node (ref "R1") (pin "1") (pinfunction "1_1") (pintype "passive"))
      (node (ref "R2") (pin "1") (pinfunction "1_1") (pintype "passive"))
    )
    (net (code "97") (name "Net-(Q1-B)") (class "Default")
      (node (ref "Q1") (pin "2") (pinfunction "B_2") (pintype "passive"))
      (node (ref "R9") (pin "2") (pinfunction "2_2") (pintype "passive"))
    )
    (net (code "98") (name "Net-(S1-P1)") (class "Default")
      (node (ref "R1") (pin "2") (pinfunction "2_2") (pintype "passive"))
      (node (ref "S1") (pin "4") (pinfunction "P1_4") (pintype "passive"))
    )
    (net (code "99") (name "Net-(U$1-{slash}POC)") (class "Default")
      (node (ref "U$1") (pin "P$99") (pinfunction "/POC_P$99") (pintype "bidirectional"))
      (node (ref "U15") (pin "8") (pinfunction "O_8") (pintype "output"))
    )
    (net (code "100") (name "Net-(U10A-I)") (class "Default")
      (node (ref "U10") (pin "13") (pinfunction "I_13") (pintype "input"))
      (node (ref "U11") (pin "5") (pinfunction "I0_5") (pintype "input"))
      (node (ref "U11") (pin "9") (pinfunction "I1_9") (pintype "input"))
      (node (ref "U20") (pin "18") (pinfunction "G1_18") (pintype "input"))
      (node (ref "U21") (pin "5") (pinfunction "Y3_5") (pintype "tri_state"))
    )
    (net (code "101") (name "Net-(U10A-O)") (class "Default")
      (node (ref "U10") (pin "12") (pinfunction "O_12") (pintype "output"))
      (node (ref "U11") (pin "12") (pinfunction "I1_12") (pintype "input"))
      (node (ref "U11") (pin "2") (pinfunction "I0_2") (pintype "input"))
    )
    (net (code "102") (name "Net-(U10B-O)") (class "Default")
      (node (ref "U10") (pin "10") (pinfunction "O_10") (pintype "output"))
      (node (ref "U21") (pin "17") (pinfunction "A4_17") (pintype "input"))
    )
    (net (code "103") (name "Net-(U10E-O)") (class "Default")
      (node (ref "U10") (pin "4") (pinfunction "O_4") (pintype "output"))
      (node (ref "U10") (pin "5") (pinfunction "I_5") (pintype "input"))
    )
    (net (code "104") (name "Net-(U11A-O)") (class "Default")
      (node (ref "U11") (pin "1") (pinfunction "O_1") (pintype "output"))
      (node (ref "U21") (pin "8") (pinfunction "A4_8") (pintype "input"))
    )
    (net (code "105") (name "Net-(U11B-O)") (class "Default")
      (node (ref "U11") (pin "4") (pinfunction "O_4") (pintype "output"))
      (node (ref "U21") (pin "11") (pinfunction "A1_11") (pintype "input"))
    )
    (net (code "106") (name "Net-(U11C-O)") (class "Default")
      (node (ref "U11") (pin "10") (pinfunction "O_10") (pintype "output"))
      (node (ref "U21") (pin "2") (pinfunction "A1_2") (pintype "input"))
    )
    (net (code "107") (name "Net-(U11D-O)") (class "Default")
      (node (ref "U11") (pin "13") (pinfunction "O_13") (pintype "output"))
      (node (ref "U21") (pin "6") (pinfunction "A3_6") (pintype "input"))
    )
    (net (code "108") (name "Net-(U14A-I2)") (class "Default")
      (node (ref "U14") (pin "13") (pinfunction "I2_13") (pintype "input"))
      (node (ref "U15") (pin "2") (pinfunction "O_2") (pintype "output"))
    )
    (net (code "109") (name "Net-(U14A-O)") (class "Default")
      (node (ref "U14") (pin "11") (pinfunction "I2_11") (pintype "input"))
      (node (ref "U14") (pin "12") (pinfunction "O_12") (pintype "output"))
    )
    (net (code "110") (name "Net-(U14B-I0)") (class "Default")
      (node (ref "U14") (pin "3") (pinfunction "I0_3") (pintype "input"))
      (node (ref "U14") (pin "4") (pinfunction "I1_4") (pintype "input"))
      (node (ref "U15") (pin "4") (pinfunction "O_4") (pintype "output"))
    )
    (net (code "111") (name "Net-(U14B-I2)") (class "Default")
      (node (ref "U14") (pin "5") (pinfunction "I2_5") (pintype "input"))
      (node (ref "U15") (pin "12") (pinfunction "O_12") (pintype "output"))
      (node (ref "U16") (pin "13") (pinfunction "I1_13") (pintype "input"))
      (node (ref "U16") (pin "2") (pinfunction "I1_2") (pintype "input"))
      (node (ref "U16") (pin "4") (pinfunction "I0_4") (pintype "input"))
    )
    (net (code "112") (name "Net-(U14C-O)") (class "Default")
      (node (ref "U14") (pin "8") (pinfunction "O_8") (pintype "output"))
      (node (ref "U25") (pin "1") (pinfunction "/CS_1") (pintype "bidirectional"))
      (node (ref "U26") (pin "1") (pinfunction "/CS_1") (pintype "bidirectional"))
    )
    (net (code "113") (name "Net-(U16A-O)") (class "Default")
      (node (ref "U16") (pin "3") (pinfunction "O_3") (pintype "output"))
      (node (ref "U17") (pin "1") (pinfunction "G_1") (pintype "input"))
    )
    (net (code "114") (name "Net-(U16D-O)") (class "Default")
      (node (ref "U16") (pin "11") (pinfunction "O_11") (pintype "output"))
      (node (ref "U17") (pin "15") (pinfunction "G_15") (pintype "input"))
    )
    (net (code "115") (name "Net-(U18B-+IN)") (class "Default")
      (node (ref "R5") (pin "1") (pinfunction "1_1") (pintype "passive"))
      (node (ref "R7") (pin "1") (pinfunction "1_1") (pintype "passive"))
      (node (ref "U18") (pin "5") (pinfunction "+IN_5") (pintype "input"))
    )
    (net (code "116") (name "Net-(U19A-QA)") (class "Default")
      (node (ref "U19") (pin "5") (pinfunction "QA_5") (pintype "bidirectional"))
      (node (ref "U20") (pin "21") (pinfunction "C_21") (pintype "input"))
    )
    (net (code "117") (name "Net-(U19A-QB)") (class "Default")
      (node (ref "U19") (pin "9") (pinfunction "QB_9") (pintype "bidirectional"))
      (node (ref "U20") (pin "20") (pinfunction "D_20") (pintype "input"))
    )
    (net (code "118") (name "Net-(U19A-QC)") (class "Default")
      (node (ref "U19") (pin "2") (pinfunction "QC_2") (pintype "bidirectional"))
      (node (ref "U20") (pin "23") (pinfunction "A_23") (pintype "input"))
    )
    (net (code "119") (name "Net-(U19A-QD)") (class "Default")
      (node (ref "U19") (pin "12") (pinfunction "QD_12") (pintype "bidirectional"))
      (node (ref "U20") (pin "22") (pinfunction "B_22") (pintype "input"))
    )
    (net (code "120") (name "Net-(U25A-{slash}DEIN)") (class "Default")
      (node (ref "U25") (pin "15") (pinfunction "/DEIN_15") (pintype "bidirectional"))
      (node (ref "U26") (pin "15") (pinfunction "/DEIN_15") (pintype "bidirectional"))
      (node (ref "U28") (pin "2") (pinfunction "I1_2") (pintype "input"))
    )
    (net (code "121") (name "Net-(U28A-O)") (class "Default")
      (node (ref "U28") (pin "3") (pinfunction "O_3") (pintype "output"))
      (node (ref "U28") (pin "4") (pinfunction "I0_4") (pintype "input"))
    )
    (net (code "122") (name "Net-(U28B-O)") (class "Default")
      (node (ref "U28") (pin "10") (pinfunction "I1_10") (pintype "input"))
      (node (ref "U28") (pin "6") (pinfunction "O_6") (pintype "output"))
      (node (ref "U28") (pin "9") (pinfunction "I0_9") (pintype "input"))
    )
    (net (code "123") (name "Net-(U28C-O)") (class "Default")
      (node (ref "U28") (pin "8") (pinfunction "O_8") (pintype "output"))
      (node (ref "U29") (pin "3") (pinfunction "CLK_3") (pintype "input"))
    )
    (net (code "124") (name "Net-(U29A-CLR)") (class "Default")
      (node (ref "U29") (pin "1") (pinfunction "CLR_1") (pintype "input"))
      (node (ref "U30") (pin "8") (pinfunction "~{Q}_8") (pintype "output"))
    )
    (net (code "125") (name "Net-(U29A-Q)") (class "Default")
      (node (ref "U29") (pin "5") (pinfunction "Q_5") (pintype "output"))
      (node (ref "U30") (pin "1") (pinfunction "CLR_1") (pintype "input"))
      (node (ref "U30") (pin "13") (pinfunction "CLR_13") (pintype "input"))
    )
    (net (code "126") (name "Net-(U30A-D)") (class "Default")
      (node (ref "U30") (pin "11") (pinfunction "CLK_11") (pintype "input"))
      (node (ref "U30") (pin "2") (pinfunction "D_2") (pintype "input"))
      (node (ref "U30") (pin "6") (pinfunction "~{Q}_6") (pintype "output"))
    )
    (net (code "127") (name "PDBIN") (class "Default")
      (node (ref "U$1") (pin "P$78") (pinfunction "PDBIN_P$78") (pintype "bidirectional"))
      (node (ref "U21") (pin "3") (pinfunction "Y4_3") (pintype "tri_state"))
    )
    (net (code "128") (name "RDY1") (class "Default")
      (node (ref "IC1") (pin "4") (pinfunction "RDY1_4") (pintype "bidirectional"))
      (node (ref "U29") (pin "6") (pinfunction "~{Q}_6") (pintype "output"))
    )
    (net (code "129") (name "READY") (class "Default")
      (node (ref "IC1") (pin "5") (pinfunction "READY_5") (pintype "bidirectional"))
      (node (ref "U12") (pin "22") (pinfunction "READY_22") (pintype "input"))
    )
    (net (code "130") (name "RESET") (class "Default")
      (node (ref "IC1") (pin "10") (pinfunction "RESET_10") (pintype "bidirectional"))
      (node (ref "R9") (pin "1") (pinfunction "1_1") (pintype "passive"))
      (node (ref "U12") (pin "21") (pinfunction "RESET_21") (pintype "input"))
      (node (ref "U15") (pin "9") (pinfunction "I_9") (pintype "input"))
    )
    (net (code "131") (name "SINP") (class "Default")
      (node (ref "U$1") (pin "P$46") (pinfunction "SINP_P$46") (pintype "bidirectional"))
      (node (ref "U21") (pin "14") (pinfunction "Y3_14") (pintype "tri_state"))
    )
    (net (code "132") (name "SMEMR") (class "Default")
      (node (ref "U$1") (pin "P$47") (pinfunction "SMEMR_P$47") (pintype "bidirectional"))
      (node (ref "U21") (pin "18") (pinfunction "Y1_18") (pintype "tri_state"))
    )
    (net (code "133") (name "SOUT") (class "Default")
      (node (ref "U$1") (pin "P$45") (pinfunction "SOUT_P$45") (pintype "bidirectional"))
      (node (ref "U21") (pin "12") (pinfunction "Y4_12") (pintype "tri_state"))
    )
    (net (code "134") (name "U1_EN") (class "Default")
      (node (ref "U1") (pin "20") (pinfunction "~{CE}_20") (pintype "input"))
      (node (ref "U17") (pin "6") (pinfunction "Y2_6") (pintype "output"))
    )
    (net (code "135") (name "U2_EN") (class "Default")
      (node (ref "U17") (pin "7") (pinfunction "Y3_7") (pintype "output"))
      (node (ref "U2") (pin "20") (pinfunction "~{CE}_20") (pintype "input"))
    )
    (net (code "136") (name "U3_EN") (class "Default")
      (node (ref "U14") (pin "6") (pinfunction "O_6") (pintype "output"))
      (node (ref "U3") (pin "20") (pinfunction "~{CE}_20") (pintype "input"))
    )
    (net (code "137") (name "U4_EN") (class "Default")
      (node (ref "U16") (pin "6") (pinfunction "O_6") (pintype "output"))
      (node (ref "U4") (pin "20") (pinfunction "~{CE}_20") (pintype "input"))
    )
    (net (code "138") (name "U5_EN") (class "Default")
      (node (ref "U16") (pin "8") (pinfunction "O_8") (pintype "output"))
      (node (ref "U5") (pin "20") (pinfunction "~{CE}_20") (pintype "input"))
    )
    (net (code "139") (name "U6_EN") (class "Default")
      (node (ref "U17") (pin "12") (pinfunction "Y0_12") (pintype "output"))
      (node (ref "U6") (pin "20") (pinfunction "~{CS1}_20") (pintype "input"))
    )
    (net (code "140") (name "U7_EN") (class "Default")
      (node (ref "U17") (pin "11") (pinfunction "Y1_11") (pintype "output"))
      (node (ref "U7") (pin "20") (pinfunction "~{CS1}_20") (pintype "input"))
    )
    (net (code "141") (name "U8_EN") (class "Default")
      (node (ref "U17") (pin "10") (pinfunction "Y2_10") (pintype "output"))
      (node (ref "U8") (pin "20") (pinfunction "~{CS1}_20") (pintype "input"))
    )
    (net (code "142") (name "U9_EN") (class "Default")
      (node (ref "U17") (pin "9") (pinfunction "Y3_9") (pintype "output"))
      (node (ref "U9") (pin "20") (pinfunction "~{CS1}_20") (pintype "input"))
    )
    (net (code "143") (name "VCC") (class "Default")
      (node (ref "CR1") (pin "C") (pinfunction "C_C") (pintype "passive"))
      (node (ref "IC1") (pin "13") (pinfunction "F/C_13") (pintype "bidirectional"))
      (node (ref "QG1") (pin "14") (pinfunction "VCC_14") (pintype "power_in"))
      (node (ref "R2") (pin "2") (pinfunction "2_2") (pintype "passive"))
      (node (ref "R3") (pin "2") (pinfunction "2_2") (pintype "passive"))
      (node (ref "R6") (pin "2") (pinfunction "2_2") (pintype "passive"))
      (node (ref "R7") (pin "2") (pinfunction "2_2") (pintype "passive"))
      (node (ref "R8") (pin "2") (pinfunction "2_2") (pintype "passive"))
      (node (ref "U$1") (pin "P$1") (pinfunction "+5V_P$1") (pintype "power_in"))
      (node (ref "U$1") (pin "P$51") (pinfunction "+5V_1_P$51") (pintype "power_in"))
      (node (ref "U1") (pin "1") (pinfunction "VPP_1") (pintype "input"))
      (node (ref "U1") (pin "27") (pinfunction "~{PGM}_27") (pintype "input"))
      (node (ref "U12") (pin "23") (pinfunction "TEST_23") (pintype "input"))
      (node (ref "U12") (pin "33") (pinfunction "MN_33") (pintype "input"))
      (node (ref "U19") (pin "13") (pinfunction "CLEAR_13") (pintype "bidirectional"))
      (node (ref "U2") (pin "1") (pinfunction "VPP_1") (pintype "input"))
      (node (ref "U2") (pin "27") (pinfunction "~{PGM}_27") (pintype "input"))
      (node (ref "U22") (pin "13") (pinfunction "A2_13") (pintype "input"))
      (node (ref "U22") (pin "6") (pinfunction "A3_6") (pintype "input"))
      (node (ref "U27") (pin "14") (pinfunction "14_14") (pintype "passive"))
      (node (ref "U29") (pin "2") (pinfunction "D_2") (pintype "input"))
      (node (ref "U29") (pin "4") (pinfunction "PRE_4") (pintype "input"))
      (node (ref "U3") (pin "1") (pinfunction "VPP_1") (pintype "input"))
      (node (ref "U30") (pin "10") (pinfunction "PRE_10") (pintype "input"))
      (node (ref "U30") (pin "12") (pinfunction "D_12") (pintype "input"))
      (node (ref "U30") (pin "4") (pinfunction "PRE_4") (pintype "input"))
      (node (ref "U4") (pin "1") (pinfunction "VPP_1") (pintype "input"))
      (node (ref "U5") (pin "1") (pinfunction "VPP_1") (pintype "input"))
      (node (ref "U6") (pin "28") (pinfunction "VCC_28") (pintype "power_in"))
      (node (ref "U7") (pin "28") (pinfunction "VCC_28") (pintype "power_in"))
      (node (ref "U8") (pin "28") (pinfunction "VCC_28") (pintype "power_in"))
      (node (ref "U9") (pin "28") (pinfunction "VCC_28") (pintype "power_in"))
    )
    (net (code "144") (name "unconnected-(IC1A-OSC-Pad12)") (class "Default")
      (node (ref "IC1") (pin "12") (pinfunction "OSC_12") (pintype "bidirectional"))
    )
    (net (code "145") (name "unconnected-(IC1A-X1-Pad17)") (class "Default")
      (node (ref "IC1") (pin "17") (pinfunction "X1_17") (pintype "bidirectional"))
    )
    (net (code "146") (name "unconnected-(IC1A-X2-Pad16)") (class "Default")
      (node (ref "IC1") (pin "16") (pinfunction "X2_16") (pintype "bidirectional"))
    )
    (net (code "147") (name "unconnected-(IC1A-{slash}AEN2-Pad7)") (class "Default")
      (node (ref "IC1") (pin "7") (pinfunction "/AEN2_7") (pintype "bidirectional"))
    )
    (net (code "148") (name "unconnected-(IC1A-{slash}ASYNC-Pad15)") (class "Default")
      (node (ref "IC1") (pin "15") (pinfunction "/ASYNC_15") (pintype "bidirectional"))
    )
    (net (code "149") (name "unconnected-(QG1-TS-Pad1)") (class "Default")
      (node (ref "QG1") (pin "1") (pinfunction "TS_1") (pintype "passive"))
    )
    (net (code "150") (name "unconnected-(S1-P-Pad3)") (class "Default")
      (node (ref "S1") (pin "3") (pinfunction "P_3") (pintype "passive"))
    )
    (net (code "151") (name "unconnected-(S1-S-Pad1)") (class "Default")
      (node (ref "S1") (pin "1") (pinfunction "S_1") (pintype "passive"))
    )
    (net (code "152") (name "unconnected-(U$1-A17-PadP$17)") (class "Default")
      (node (ref "U$1") (pin "P$17") (pinfunction "A17_P$17") (pintype "bidirectional"))
    )
    (net (code "153") (name "unconnected-(U$1-DI2_D10-PadP$41)") (class "Default")
      (node (ref "U$1") (pin "P$41") (pinfunction "DI2_D10_P$41") (pintype "bidirectional"))
    )
    (net (code "154") (name "unconnected-(U$1-DI3_D11-PadP$42)") (class "Default")
      (node (ref "U$1") (pin "P$42") (pinfunction "DI3_D11_P$42") (pintype "bidirectional"))
    )
    (net (code "155") (name "unconnected-(U$1-DI7_D15-PadP$43)") (class "Default")
      (node (ref "U$1") (pin "P$43") (pinfunction "DI7_D15_P$43") (pintype "bidirectional"))
    )
    (net (code "156") (name "unconnected-(U$1-DO0_D0-PadP$36)") (class "Default")
      (node (ref "U$1") (pin "P$36") (pinfunction "DO0_D0_P$36") (pintype "bidirectional"))
    )
    (net (code "157") (name "unconnected-(U$1-DO1_D1-PadP$35)") (class "Default")
      (node (ref "U$1") (pin "P$35") (pinfunction "DO1_D1_P$35") (pintype "bidirectional"))
    )
    (net (code "158") (name "unconnected-(U$1-DO4_D4-PadP$38)") (class "Default")
      (node (ref "U$1") (pin "P$38") (pinfunction "DO4_D4_P$38") (pintype "bidirectional"))
    )
    (net (code "159") (name "unconnected-(U$1-DO5_D5-PadP$39)") (class "Default")
      (node (ref "U$1") (pin "P$39") (pinfunction "DO5_D5_P$39") (pintype "bidirectional"))
    )
    (net (code "160") (name "unconnected-(U$1-DO6_D6-PadP$40)") (class "Default")
      (node (ref "U$1") (pin "P$40") (pinfunction "DO6_D6_P$40") (pintype "bidirectional"))
    )
    (net (code "161") (name "unconnected-(U$1-GND_3-PadP$53)") (class "Default")
      (node (ref "U$1") (pin "P$53") (pinfunction "GND_3_P$53") (pintype "power_in"))
    )
    (net (code "162") (name "unconnected-(U$1-MCLOCK-PadP$24)") (class "Default")
      (node (ref "U$1") (pin "P$24") (pinfunction "MCLOCK_P$24") (pintype "bidirectional"))
    )
    (net (code "163") (name "unconnected-(U$1-PHLDA-PadP$26)") (class "Default")
      (node (ref "U$1") (pin "P$26") (pinfunction "PHLDA_P$26") (pintype "bidirectional"))
    )
    (net (code "164") (name "unconnected-(U$1-PINTE-PadP$28)") (class "Default")
      (node (ref "U$1") (pin "P$28") (pinfunction "PINTE_P$28") (pintype "bidirectional"))
    )
    (net (code "165") (name "unconnected-(U$1-PRDY-PadP$72)") (class "Default")
      (node (ref "U$1") (pin "P$72") (pinfunction "PRDY_P$72") (pintype "bidirectional"))
    )
    (net (code "166") (name "unconnected-(U$1-PSYNC-PadP$76)") (class "Default")
      (node (ref "U$1") (pin "P$76") (pinfunction "PSYNC_P$76") (pintype "bidirectional"))
    )
    (net (code "167") (name "unconnected-(U$1-PWAIT-PadP$27)") (class "Default")
      (node (ref "U$1") (pin "P$27") (pinfunction "PWAIT_P$27") (pintype "bidirectional"))
    )
    (net (code "168") (name "unconnected-(U$1-RUN-PadP$71)") (class "Default")
      (node (ref "U$1") (pin "P$71") (pinfunction "RUN_P$71") (pintype "bidirectional"))
    )
    (net (code "169") (name "unconnected-(U$1-SHLTA-PadP$48)") (class "Default")
      (node (ref "U$1") (pin "P$48") (pinfunction "SHLTA_P$48") (pintype "bidirectional"))
    )
    (net (code "170") (name "unconnected-(U$1-SINTA-PadP$96)") (class "Default")
      (node (ref "U$1") (pin "P$96") (pinfunction "SINTA_P$96") (pintype "bidirectional"))
    )
    (net (code "171") (name "unconnected-(U$1-SM1-PadP$44)") (class "Default")
      (node (ref "U$1") (pin "P$44") (pinfunction "SM1_P$44") (pintype "bidirectional"))
    )
    (net (code "172") (name "unconnected-(U$1-SS-PadP$21)") (class "Default")
      (node (ref "U$1") (pin "P$21") (pinfunction "SS_P$21") (pintype "bidirectional"))
    )
    (net (code "173") (name "unconnected-(U$1-XRDY-PadP$3)") (class "Default")
      (node (ref "U$1") (pin "P$3") (pinfunction "XRDY_P$3") (pintype "bidirectional"))
    )
    (net (code "174") (name "unconnected-(U$1-{slash}ADSB-PadP$22)") (class "Default")
      (node (ref "U$1") (pin "P$22") (pinfunction "/ADSB_P$22") (pintype "bidirectional"))
    )
    (net (code "175") (name "unconnected-(U$1-{slash}CDSB-PadP$19)") (class "Default")
      (node (ref "U$1") (pin "P$19") (pinfunction "/CDSB_P$19") (pintype "bidirectional"))
    )
    (net (code "176") (name "unconnected-(U$1-{slash}DMA0-PadP$55)") (class "Default")
      (node (ref "U$1") (pin "P$55") (pinfunction "/DMA0_P$55") (pintype "bidirectional"))
    )
    (net (code "177") (name "unconnected-(U$1-{slash}DODSB-PadP$23)") (class "Default")
      (node (ref "U$1") (pin "P$23") (pinfunction "/DODSB_P$23") (pintype "bidirectional"))
    )
    (net (code "178") (name "unconnected-(U$1-{slash}ERROR-PadP$98)") (class "Default")
      (node (ref "U$1") (pin "P$98") (pinfunction "/ERROR_P$98") (pintype "bidirectional"))
    )
    (net (code "179") (name "unconnected-(U$1-{slash}PHANTOM-PadP$67)") (class "Default")
      (node (ref "U$1") (pin "P$67") (pinfunction "/PHANTOM_P$67") (pintype "bidirectional"))
    )
    (net (code "180") (name "unconnected-(U$1-{slash}PHOLD-PadP$74)") (class "Default")
      (node (ref "U$1") (pin "P$74") (pinfunction "/PHOLD_P$74") (pintype "bidirectional"))
    )
    (net (code "181") (name "unconnected-(U$1-{slash}PRESET-PadP$75)") (class "Default")
      (node (ref "U$1") (pin "P$75") (pinfunction "/PRESET_P$75") (pintype "bidirectional"))
    )
    (net (code "182") (name "unconnected-(U$1-{slash}PS-PadP$69)") (class "Default")
      (node (ref "U$1") (pin "P$69") (pinfunction "/PS_P$69") (pintype "bidirectional"))
    )
    (net (code "183") (name "unconnected-(U$1-{slash}SDSB-PadP$18)") (class "Default")
      (node (ref "U$1") (pin "P$18") (pinfunction "/SDSB_P$18") (pintype "bidirectional"))
    )
    (net (code "184") (name "unconnected-(U$1-{slash}SLAVE_CLR-PadP$54)") (class "Default")
      (node (ref "U$1") (pin "P$54") (pinfunction "/SLAVE_CLR_P$54") (pintype "bidirectional"))
    )
    (net (code "185") (name "unconnected-(U$1-{slash}SWO-PadP$97)") (class "Default")
      (node (ref "U$1") (pin "P$97") (pinfunction "/SWO_P$97") (pintype "bidirectional"))
    )
    (net (code "186") (name "unconnected-(U$1-{slash}VI0-PadP$4)") (class "Default")
      (node (ref "U$1") (pin "P$4") (pinfunction "/VI0_P$4") (pintype "bidirectional"))
    )
    (net (code "187") (name "unconnected-(U$1-{slash}VI1-PadP$5)") (class "Default")
      (node (ref "U$1") (pin "P$5") (pinfunction "/VI1_P$5") (pintype "bidirectional"))
    )
    (net (code "188") (name "unconnected-(U$1-{slash}VI2-PadP$6)") (class "Default")
      (node (ref "U$1") (pin "P$6") (pinfunction "/VI2_P$6") (pintype "bidirectional"))
    )
    (net (code "189") (name "unconnected-(U$1-{slash}VI3-PadP$7)") (class "Default")
      (node (ref "U$1") (pin "P$7") (pinfunction "/VI3_P$7") (pintype "bidirectional"))
    )
    (net (code "190") (name "unconnected-(U$1-{slash}VI4-PadP$8)") (class "Default")
      (node (ref "U$1") (pin "P$8") (pinfunction "/VI4_P$8") (pintype "bidirectional"))
    )
    (net (code "191") (name "unconnected-(U$1-{slash}VI5-PadP$9)") (class "Default")
      (node (ref "U$1") (pin "P$9") (pinfunction "/VI5_P$9") (pintype "bidirectional"))
    )
    (net (code "192") (name "unconnected-(U$1-{slash}VI6-PadP$10)") (class "Default")
      (node (ref "U$1") (pin "P$10") (pinfunction "/VI6_P$10") (pintype "bidirectional"))
    )
    (net (code "193") (name "unconnected-(U$1-{slash}VI7-PadP$11)") (class "Default")
      (node (ref "U$1") (pin "P$11") (pinfunction "/VI7_P$11") (pintype "bidirectional"))
    )
    (net (code "194") (name "unconnected-(U6-NC-Pad1)") (class "Default")
      (node (ref "U6") (pin "1") (pinfunction "NC_1") (pintype "no_connect"))
    )
    (net (code "195") (name "unconnected-(U7-NC-Pad1)") (class "Default")
      (node (ref "U7") (pin "1") (pinfunction "NC_1") (pintype "no_connect"))
    )
    (net (code "196") (name "unconnected-(U8-NC-Pad1)") (class "Default")
      (node (ref "U8") (pin "1") (pinfunction "NC_1") (pintype "no_connect"))
    )
    (net (code "197") (name "unconnected-(U9-NC-Pad1)") (class "Default")
      (node (ref "U9") (pin "1") (pinfunction "NC_1") (pintype "no_connect"))
    )
    (net (code "198") (name "unconnected-(U12A-DEN-Pad26)") (class "Default")
      (node (ref "U12") (pin "26") (pinfunction "DEN_26") (pintype "output"))
    )
    (net (code "199") (name "unconnected-(U12A-DT{slash}~{R}-Pad27)") (class "Default")
      (node (ref "U12") (pin "27") (pinfunction "DT/~{R}_27") (pintype "output"))
    )
    (net (code "200") (name "unconnected-(U12A-SSO-Pad34)") (class "Default")
      (node (ref "U12") (pin "34") (pinfunction "SSO_34") (pintype "output"))
    )
    (net (code "201") (name "unconnected-(U17A-Y0-Pad4)") (class "Default")
      (node (ref "U17") (pin "4") (pinfunction "Y0_4") (pintype "output"))
    )
    (net (code "202") (name "unconnected-(U17A-Y1-Pad5)") (class "Default")
      (node (ref "U17") (pin "5") (pinfunction "Y1_5") (pintype "output"))
    )
    (net (code "203") (name "unconnected-(U27-Pad1)") (class "Default")
      (node (ref "U27") (pin "1") (pinfunction "1_1") (pintype "passive"))
    )
    (net (code "204") (name "unconnected-(U27-Pad11)") (class "Default")
      (node (ref "U27") (pin "11") (pinfunction "11_11") (pintype "passive"))
    )
    (net (code "205") (name "unconnected-(U27-Pad12)") (class "Default")
      (node (ref "U27") (pin "12") (pinfunction "12_12") (pintype "passive"))
    )
    (net (code "206") (name "unconnected-(U27-Pad13)") (class "Default")
      (node (ref "U27") (pin "13") (pinfunction "13_13") (pintype "passive"))
    )
    (net (code "207") (name "unconnected-(U30A-Q-Pad5)") (class "Default")
      (node (ref "U30") (pin "5") (pinfunction "Q_5") (pintype "output"))
    )
    (net (code "208") (name "unconnected-(U30B-Q-Pad9)") (class "Default")
      (node (ref "U30") (pin "9") (pinfunction "Q_9") (pintype "output"))
    )
    (net (code "209") (name "{slash}ALE") (class "Default")
      (node (ref "U10") (pin "2") (pinfunction "O_2") (pintype "output"))
      (node (ref "U19") (pin "1") (pinfunction "LOAD_1") (pintype "bidirectional"))
      (node (ref "U23") (pin "11") (pinfunction "CLK_11") (pintype "input"))
    )
    (net (code "210") (name "{slash}OE") (class "Default")
      (node (ref "U1") (pin "22") (pinfunction "~{OE}_22") (pintype "input"))
      (node (ref "U10") (pin "11") (pinfunction "I_11") (pintype "input"))
      (node (ref "U11") (pin "11") (pinfunction "I0_11") (pintype "input"))
      (node (ref "U11") (pin "8") (pinfunction "I0_8") (pintype "input"))
      (node (ref "U2") (pin "22") (pinfunction "~{OE}_22") (pintype "input"))
      (node (ref "U21") (pin "16") (pinfunction "Y2_16") (pintype "tri_state"))
      (node (ref "U3") (pin "22") (pinfunction "~{OE}_22") (pintype "input"))
      (node (ref "U4") (pin "22") (pinfunction "~{OE}_22") (pintype "input"))
      (node (ref "U5") (pin "22") (pinfunction "~{OE}_22") (pintype "input"))
      (node (ref "U6") (pin "22") (pinfunction "~{OE}_22") (pintype "input"))
      (node (ref "U7") (pin "22") (pinfunction "~{OE}_22") (pintype "input"))
      (node (ref "U8") (pin "22") (pinfunction "~{OE}_22") (pintype "input"))
      (node (ref "U9") (pin "22") (pinfunction "~{OE}_22") (pintype "input"))
    )
    (net (code "211") (name "{slash}PINT") (class "Default")
      (node (ref "U$1") (pin "P$73") (pinfunction "/PINT_P$73") (pintype "bidirectional"))
      (node (ref "U15") (pin "11") (pinfunction "I_11") (pintype "input"))
      (node (ref "U27") (pin "2") (pinfunction "2_2") (pintype "passive"))
    )
    (net (code "212") (name "{slash}PSTVAL") (class "Default")
      (node (ref "U$1") (pin "P$25") (pinfunction "/PSTVAL_P$25") (pintype "bidirectional"))
      (node (ref "U10") (pin "6") (pinfunction "O_6") (pintype "output"))
    )
    (net (code "213") (name "{slash}PWR") (class "Default")
      (node (ref "U$1") (pin "P$77") (pinfunction "/PWR_P$77") (pintype "bidirectional"))
      (node (ref "U11") (pin "3") (pinfunction "I1_3") (pintype "input"))
      (node (ref "U11") (pin "6") (pinfunction "I1_6") (pintype "input"))
      (node (ref "U21") (pin "7") (pinfunction "Y2_7") (pintype "tri_state"))
      (node (ref "U28") (pin "1") (pinfunction "I0_1") (pintype "input"))
      (node (ref "U6") (pin "27") (pinfunction "~{WE}_27") (pintype "input"))
      (node (ref "U7") (pin "27") (pinfunction "~{WE}_27") (pintype "input"))
      (node (ref "U8") (pin "27") (pinfunction "~{WE}_27") (pintype "input"))
      (node (ref "U9") (pin "27") (pinfunction "~{WE}_27") (pintype "input"))
    )
    (net (code "214") (name "{slash}RD") (class "Default")
      (node (ref "U12") (pin "32") (pinfunction "RD_32") (pintype "output"))
      (node (ref "U21") (pin "4") (pinfunction "A2_4") (pintype "input"))
    )
    (net (code "215") (name "{slash}WR") (class "Default")
      (node (ref "U12") (pin "29") (pinfunction "WR_29") (pintype "output"))
      (node (ref "U21") (pin "13") (pinfunction "A2_13") (pintype "input"))
    )
  )
)
